# UMN_HASP_2015_Front_End_Board2.net
KiCad netlist of a schematic drawn in EAGLE
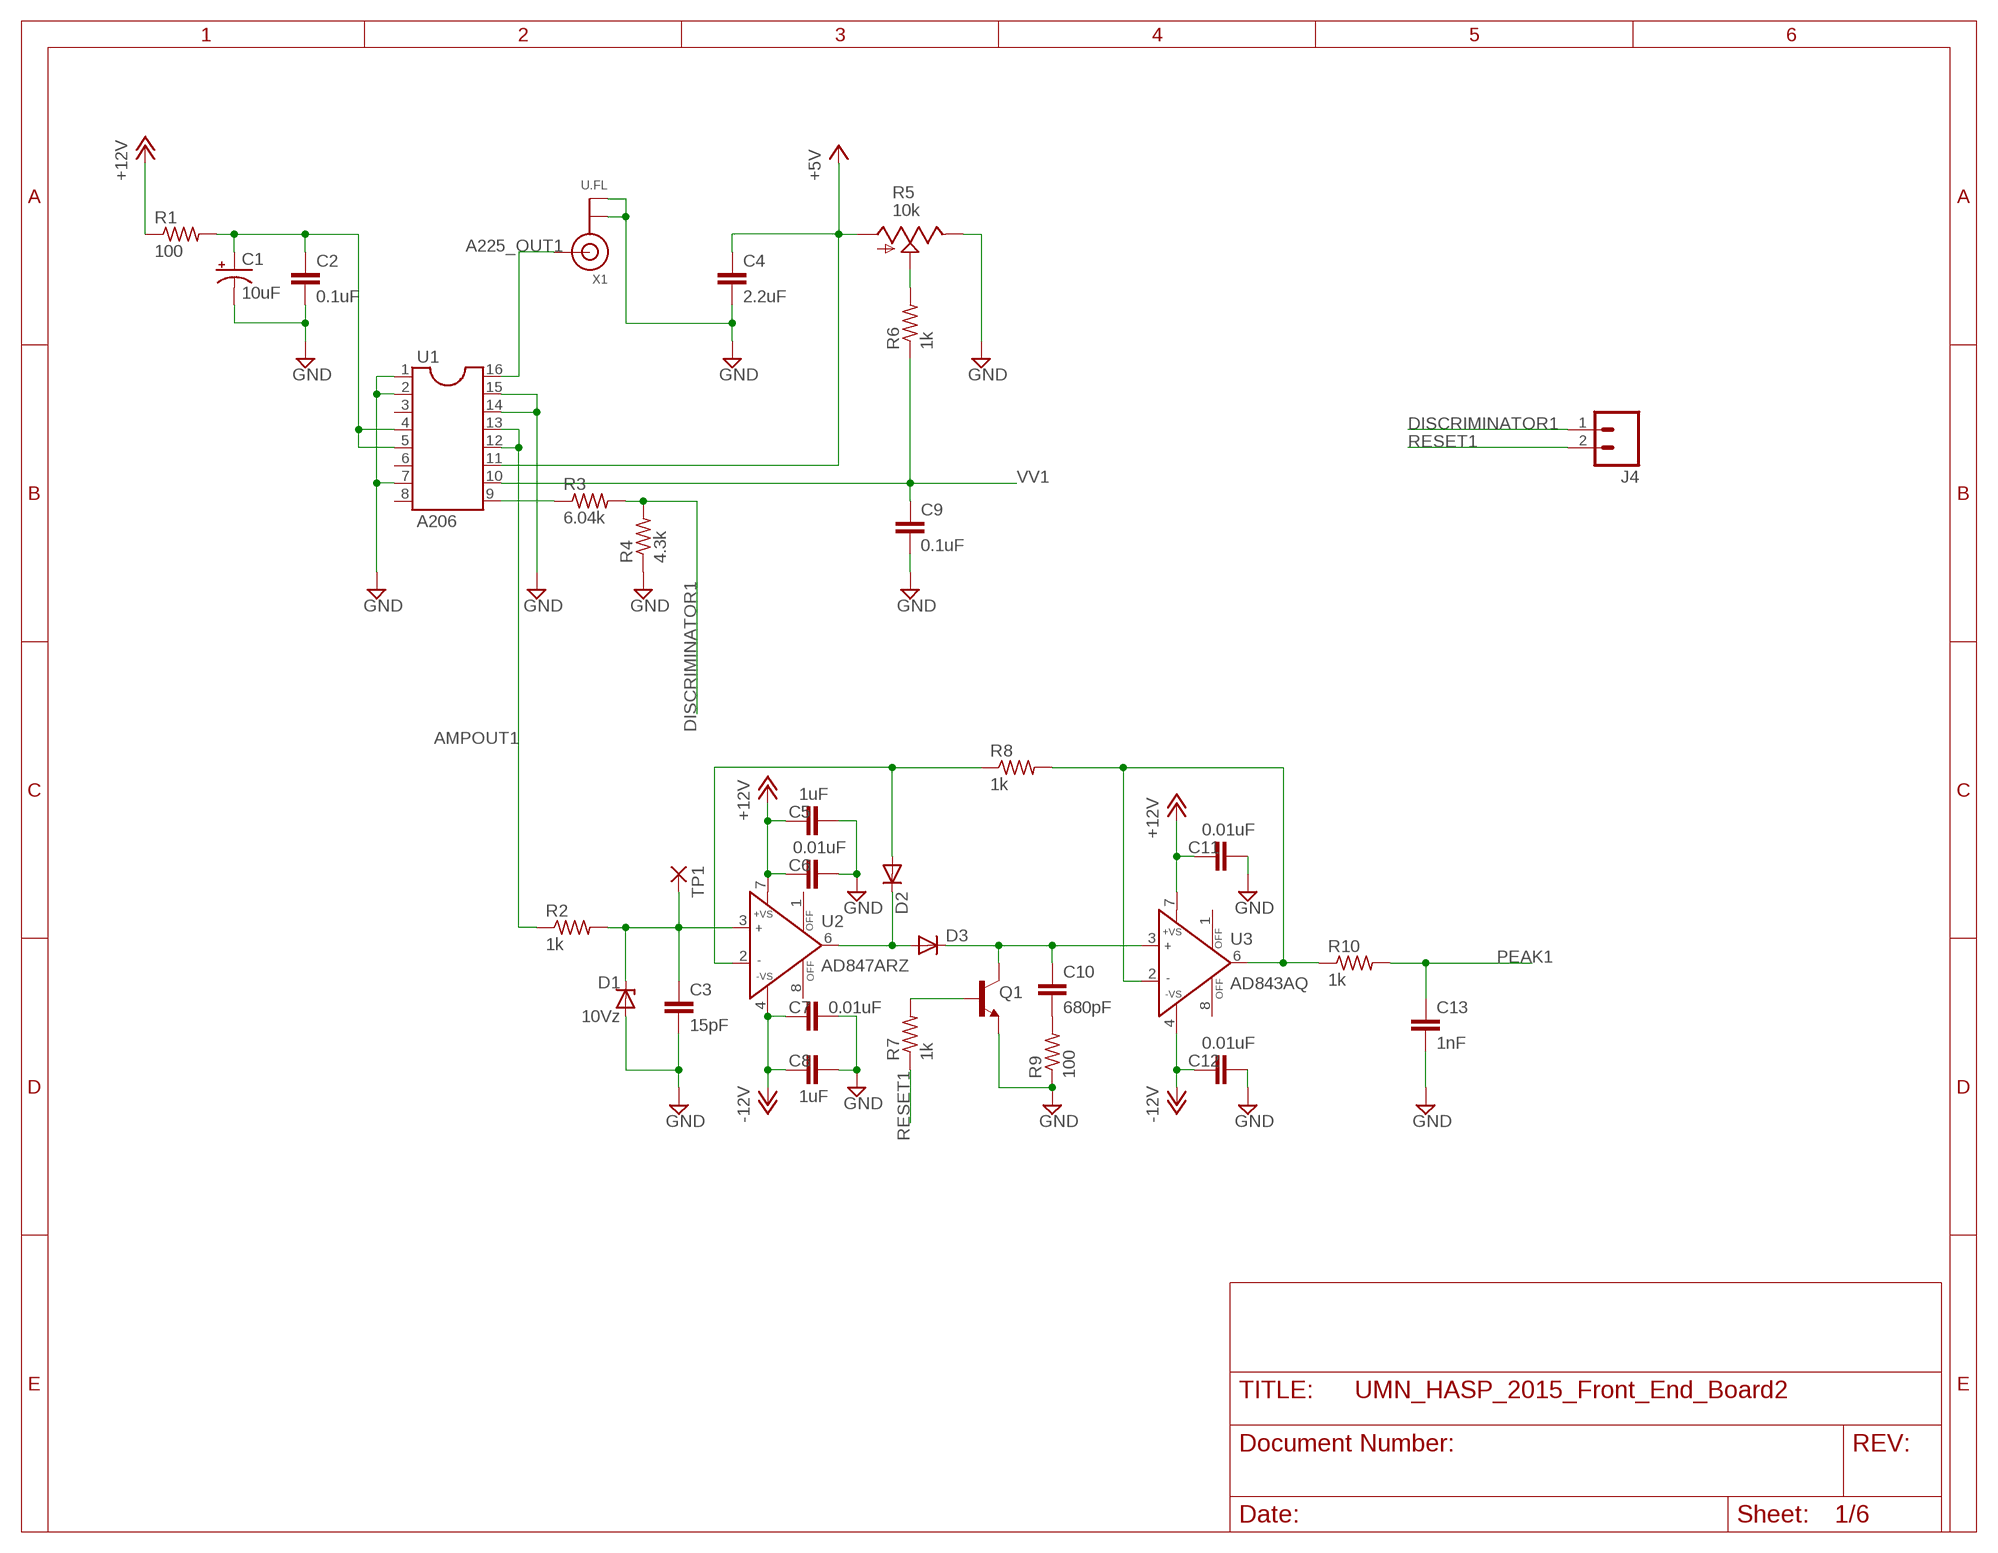
[diagram p0: schematic, sheet 1]
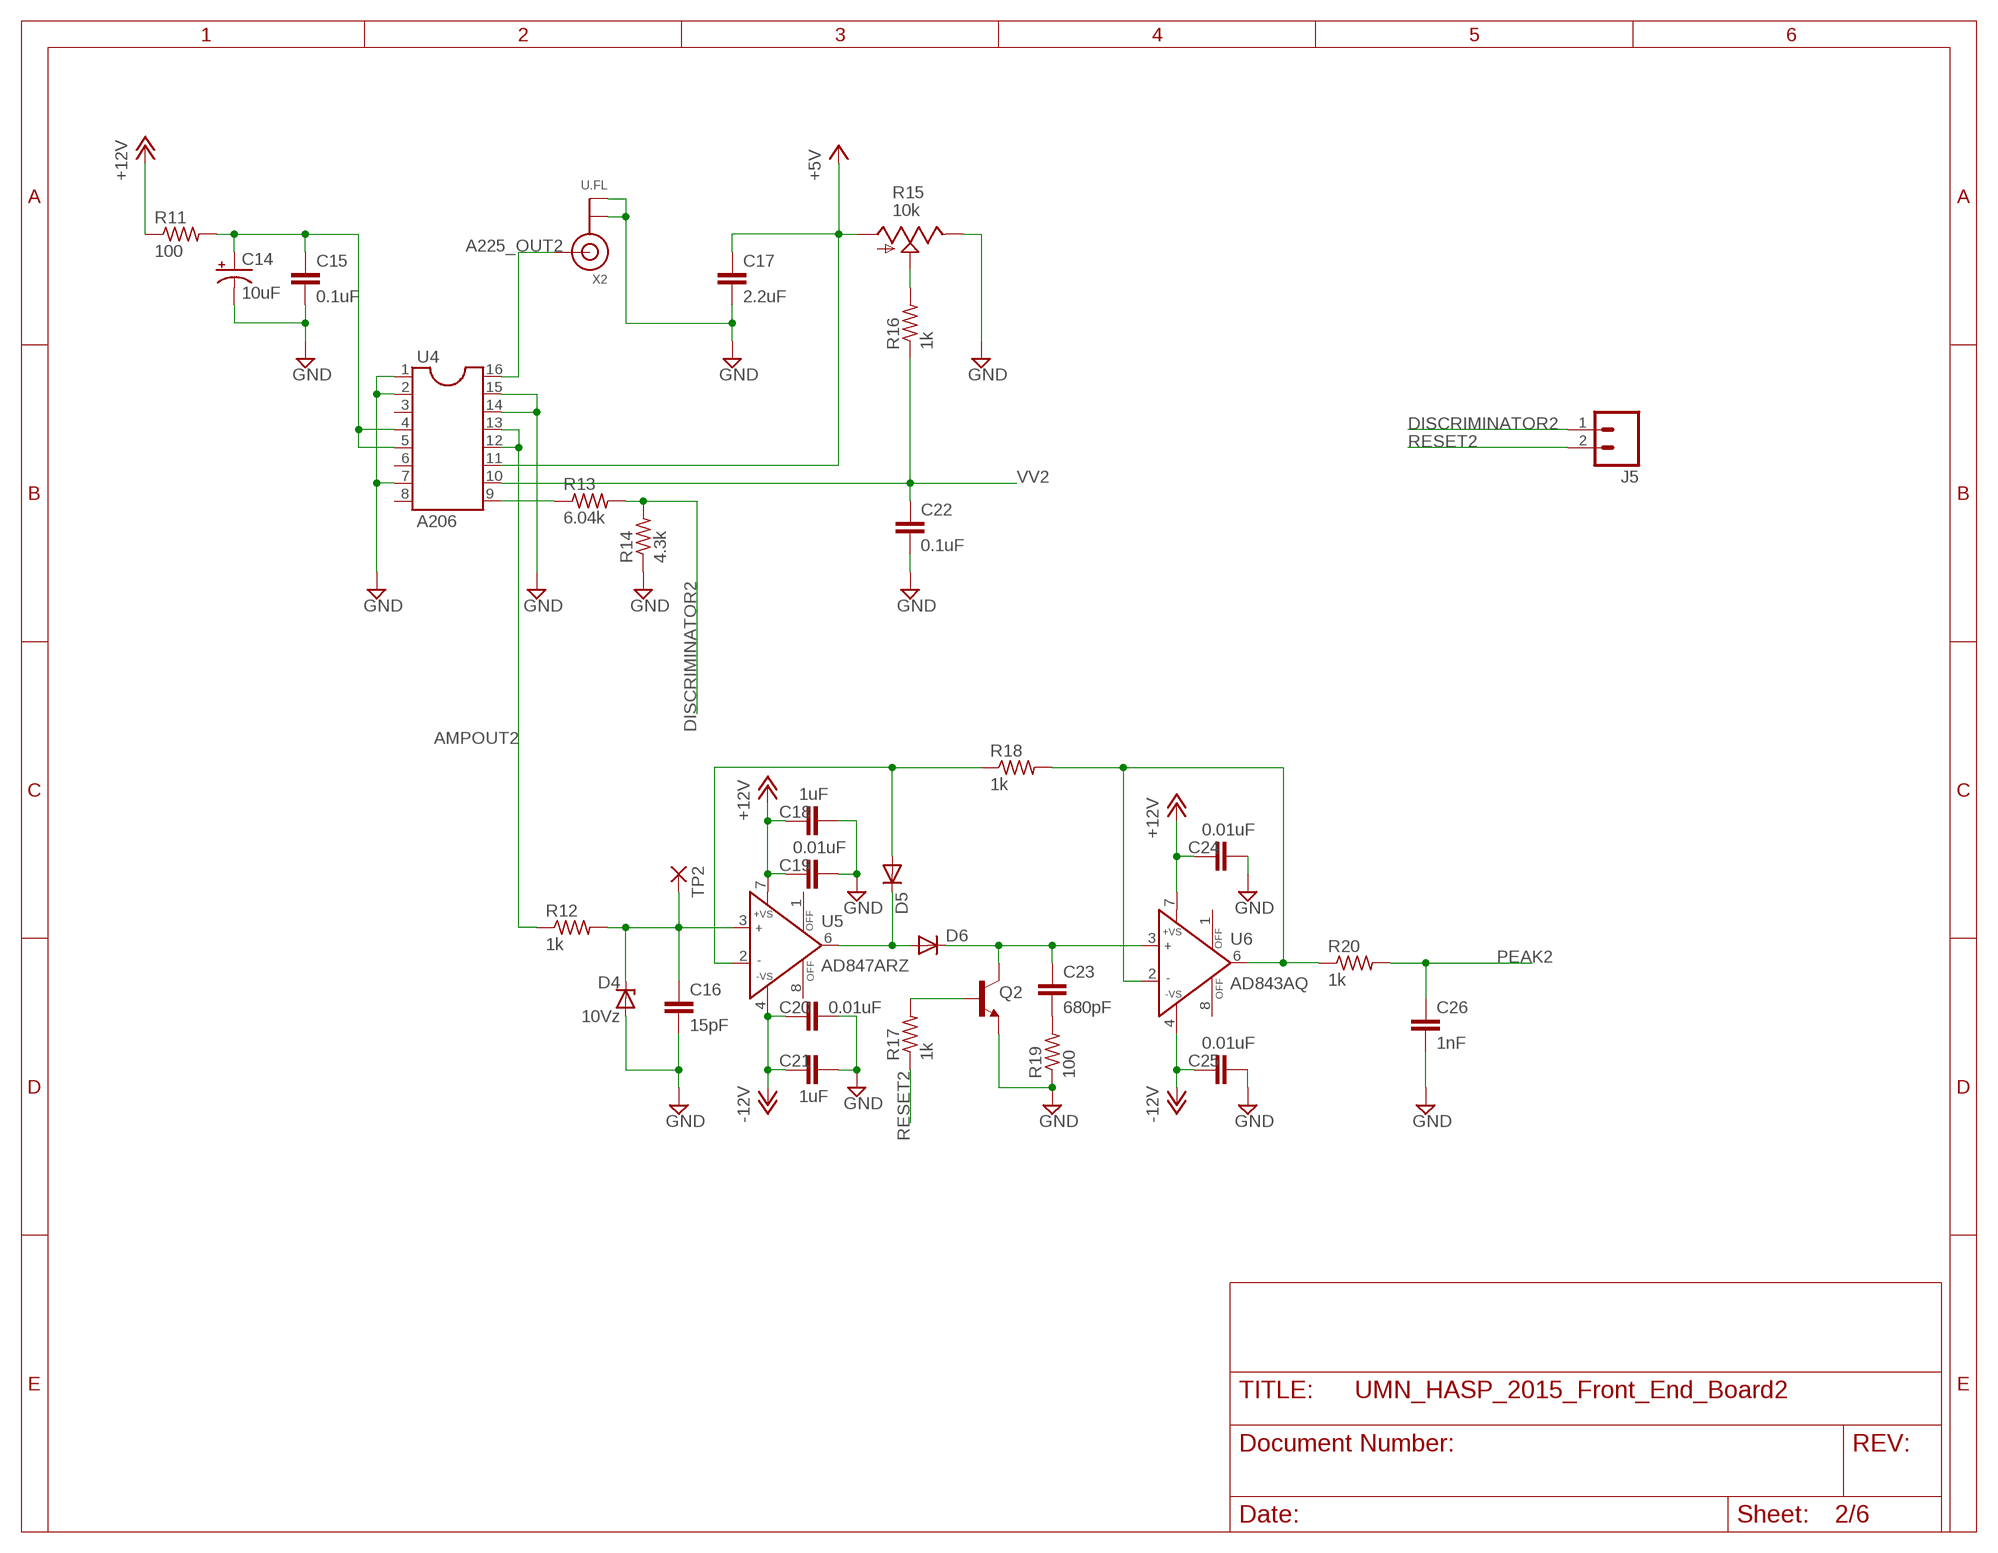
[diagram p1: schematic, sheet 2]
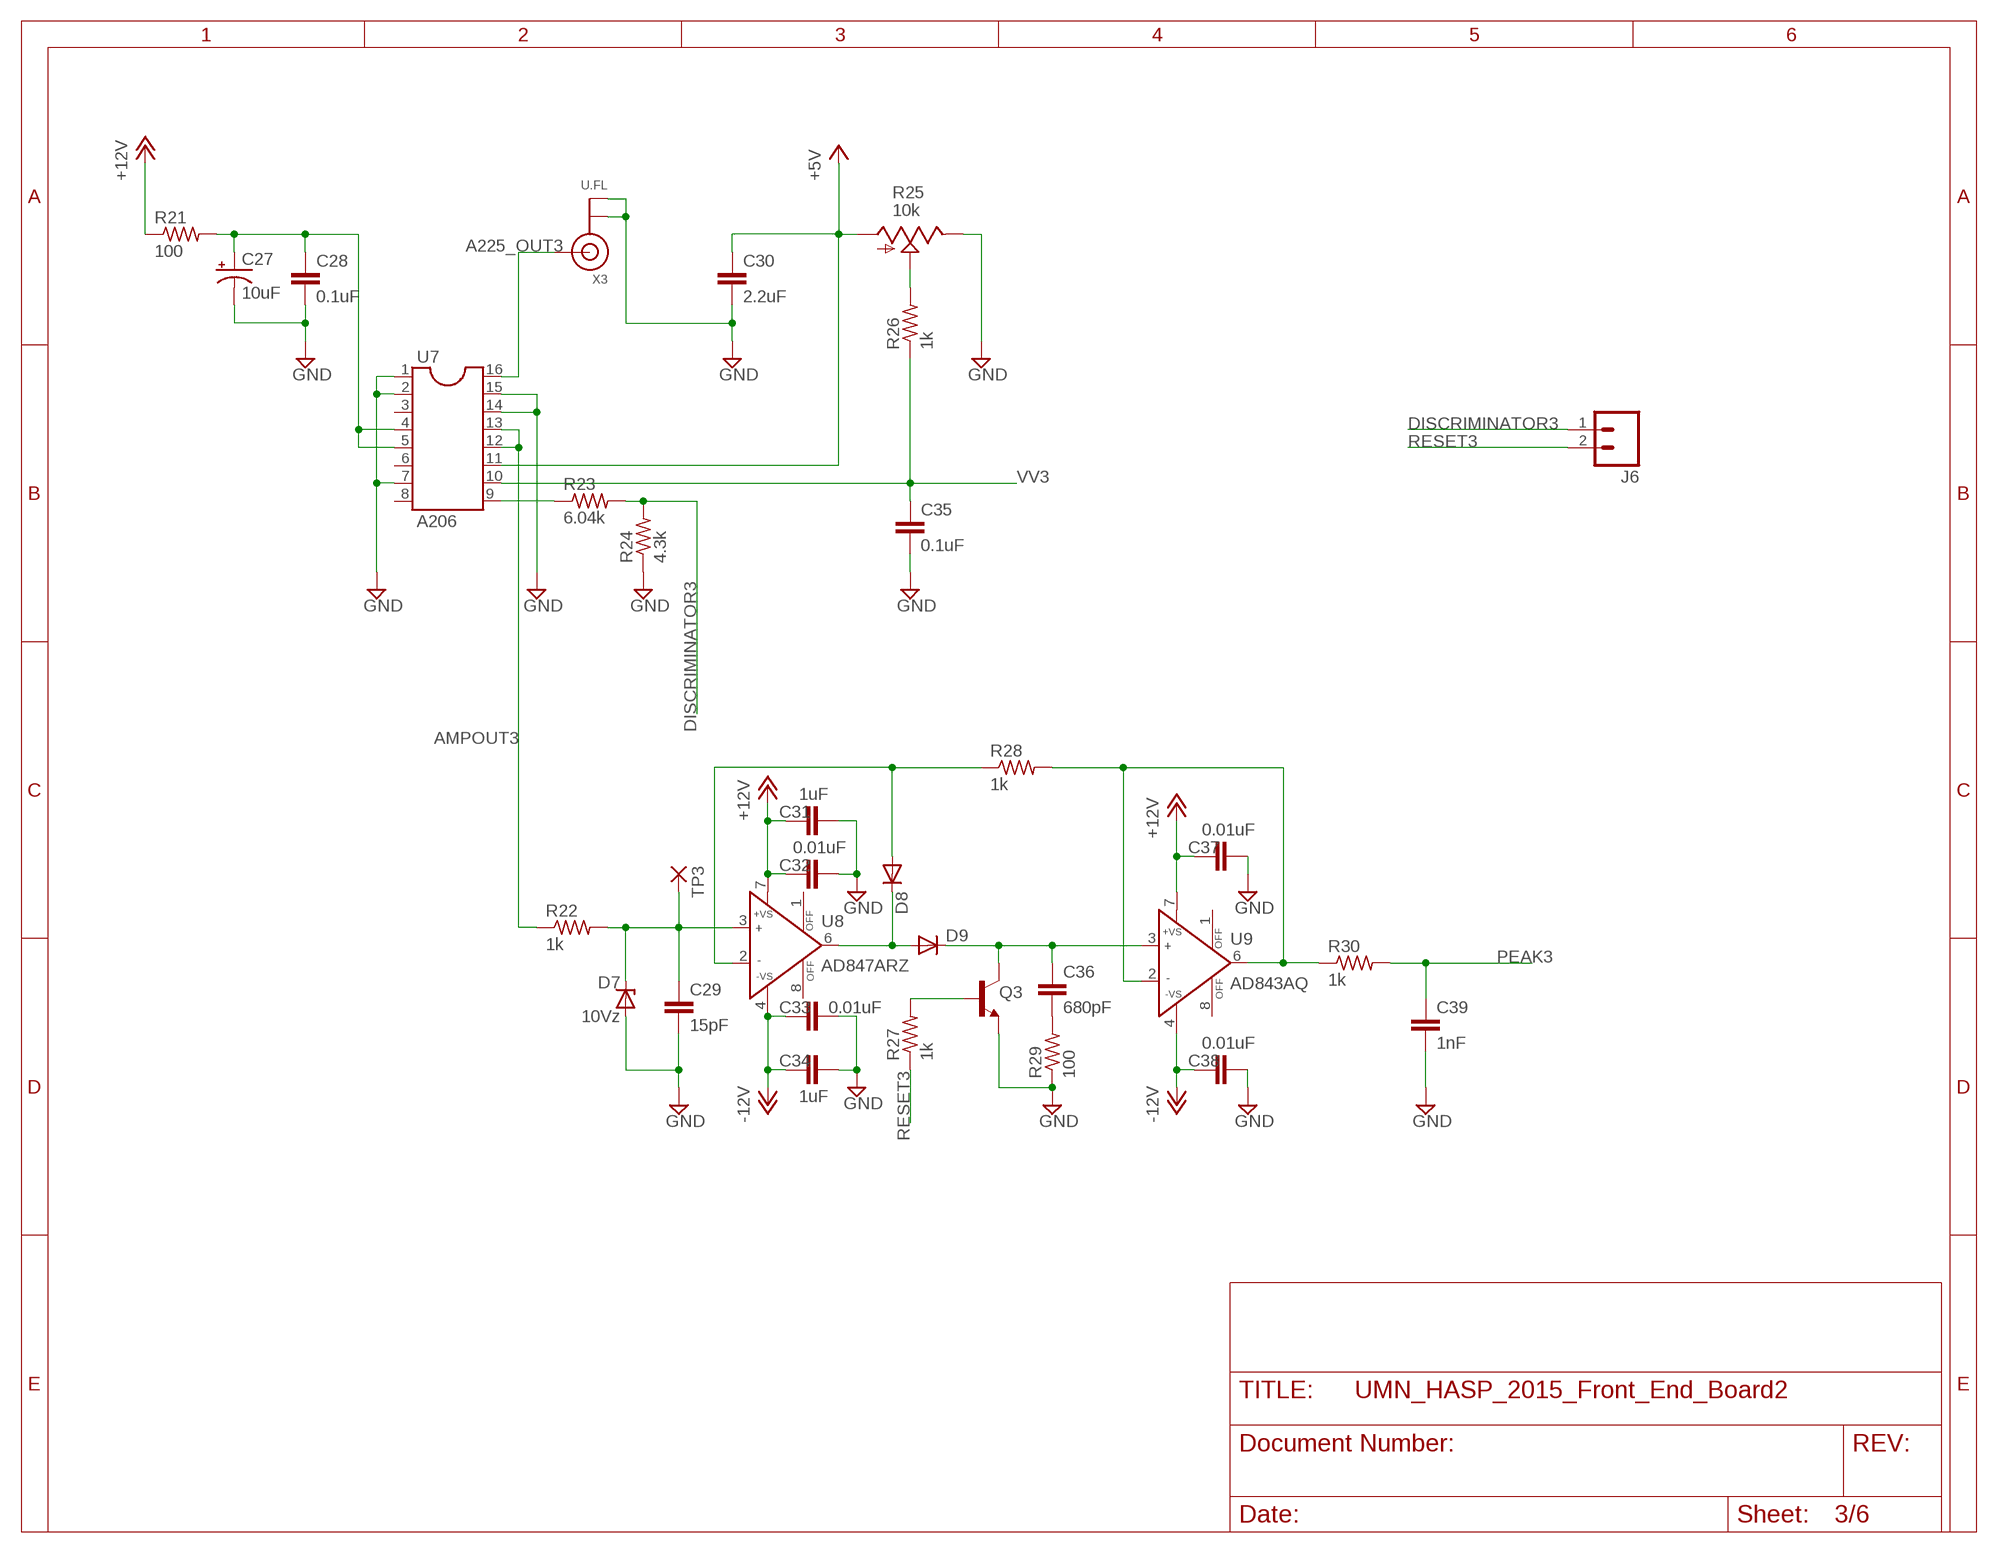
[diagram p2: schematic, sheet 3]
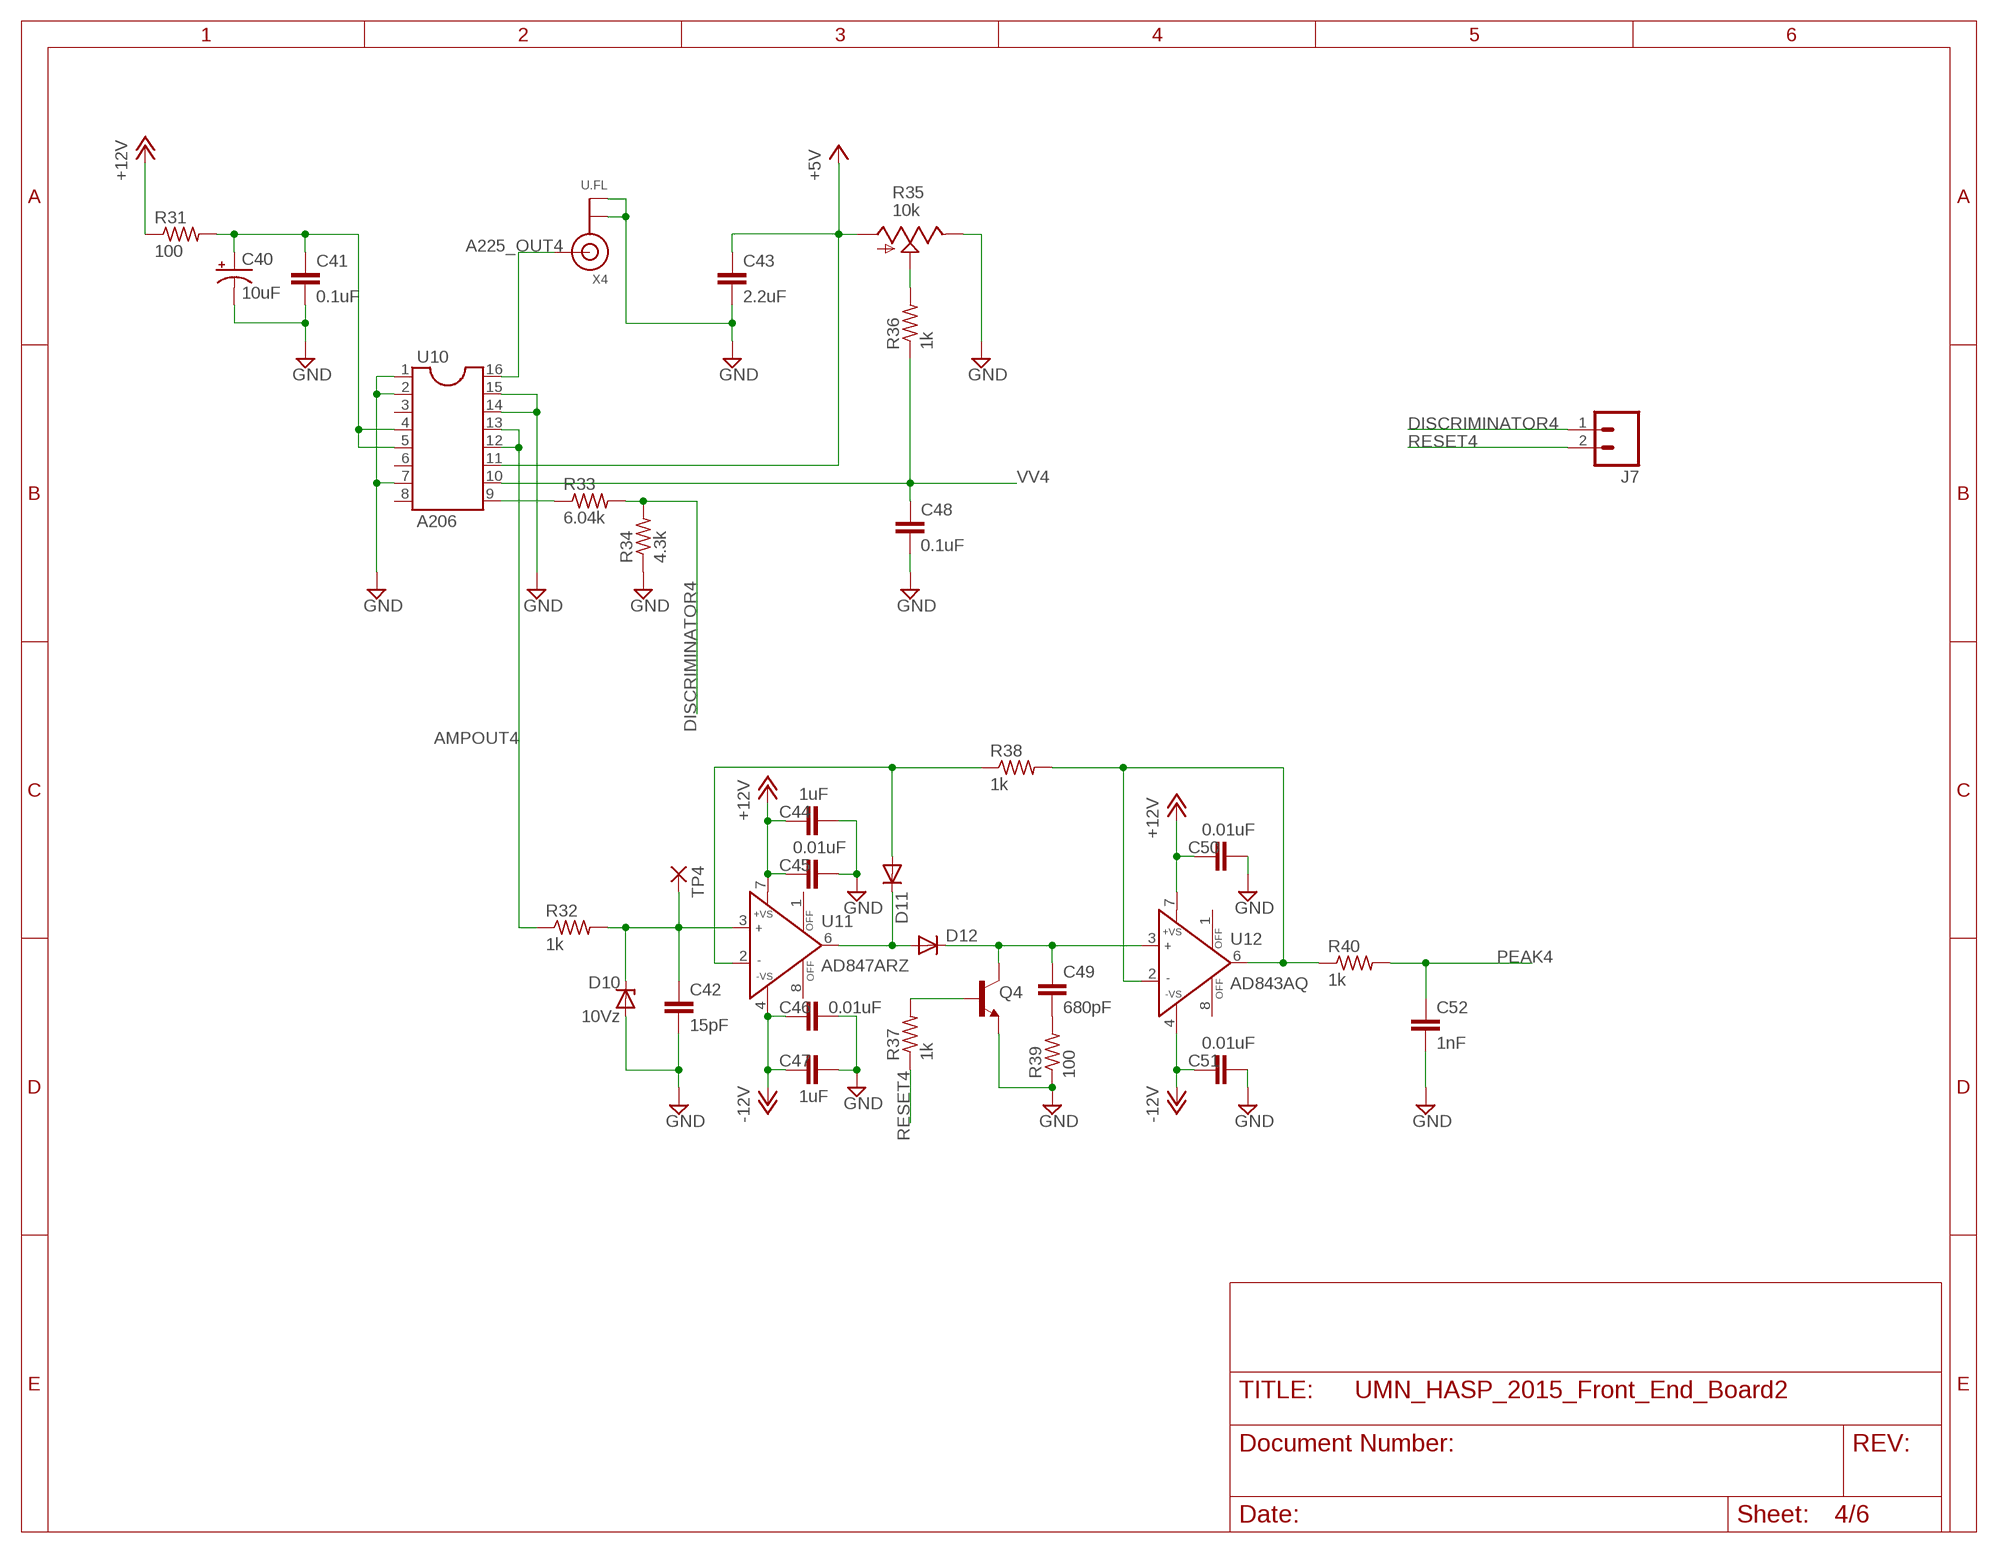
[diagram p3: schematic, sheet 4]
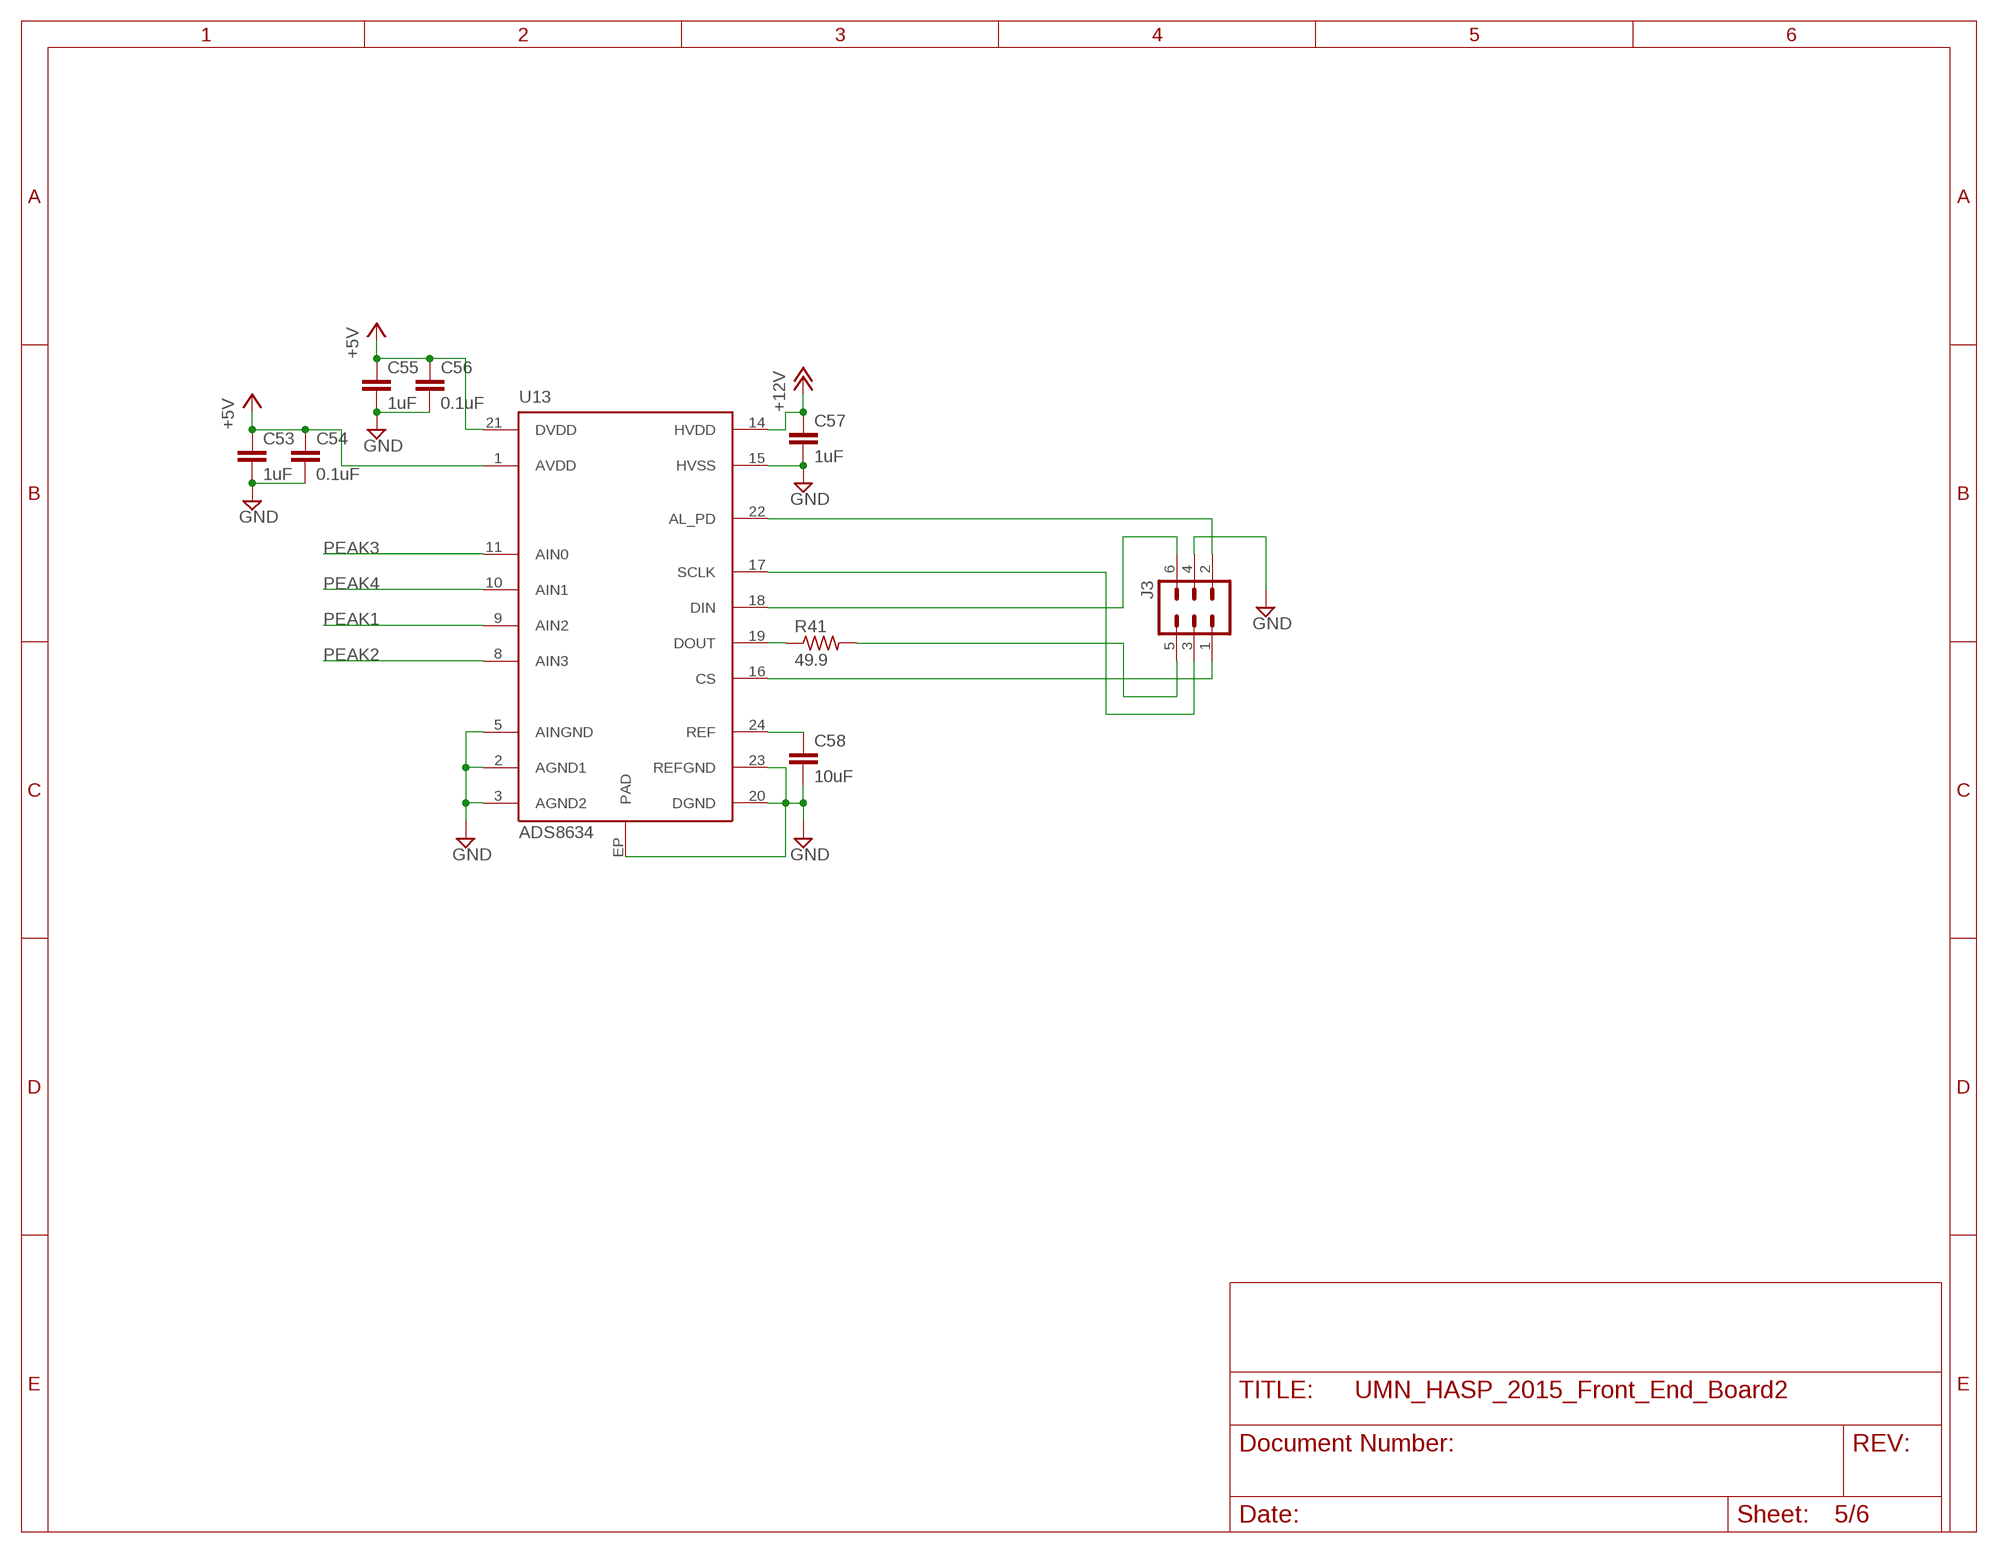
[diagram p4: schematic, sheet 5]
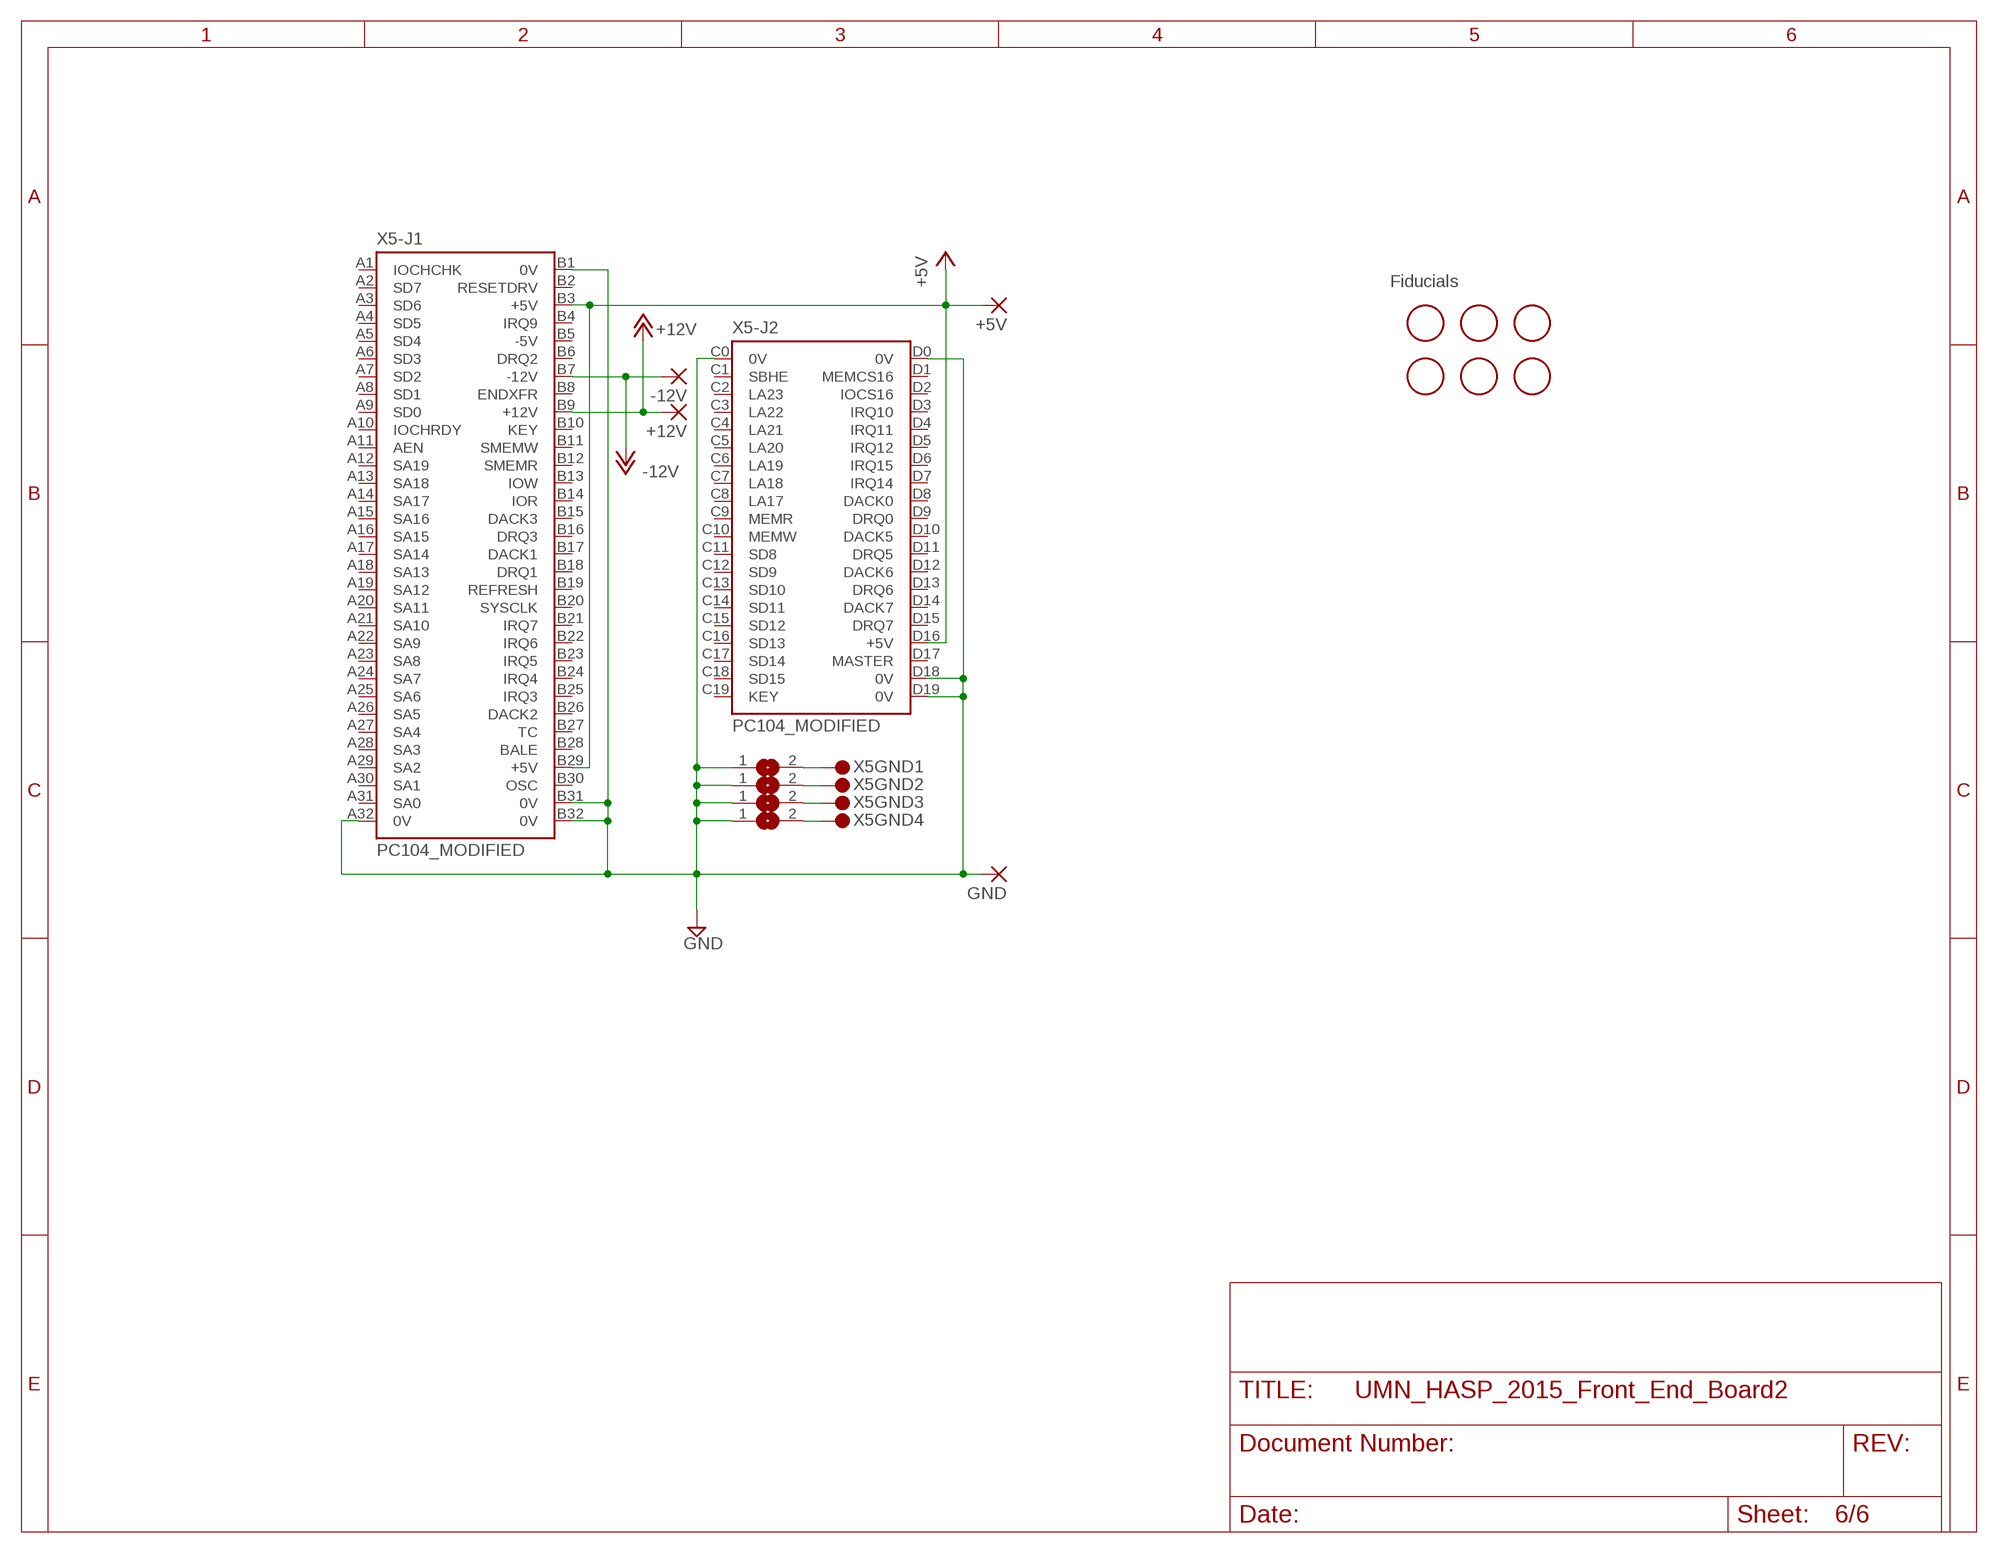
[diagram p5: schematic, sheet 6]

(export (version "E")
  (design (tool "Eeschema 10.0.6"))
  (components
    (comp (ref "C53")
      (value "1uF")
      (footprint "eagle-import:C0402K")
      (libsource (lib "eagle-import") (part "C-EUC0402K"))
    )
    (comp (ref "C54")
      (value "0.1uF")
      (footprint "eagle-import:C0402K")
      (libsource (lib "eagle-import") (part "C-EUC0402K"))
    )
    (comp (ref "C55")
      (value "1uF")
      (footprint "eagle-import:C0402K")
      (libsource (lib "eagle-import") (part "C-EUC0402K"))
    )
    (comp (ref "C56")
      (value "0.1uF")
      (footprint "eagle-import:C0402K")
      (libsource (lib "eagle-import") (part "C-EUC0402K"))
    )
    (comp (ref "C57")
      (value "1uF")
      (footprint "eagle-import:C0402K")
      (libsource (lib "eagle-import") (part "C-EUC0402K"))
    )
    (comp (ref "C58")
      (value "10uF")
      (footprint "eagle-import:C0603K")
      (libsource (lib "eagle-import") (part "C-EUC0603K"))
    )
    (comp (ref "J3")
      (value "MA03-2")
      (footprint "eagle-import:MA03-2")
      (libsource (lib "eagle-import") (part "MA03-2"))
    )
    (comp (ref "R41")
      (value "49.9")
      (footprint "eagle-import:R0402")
      (libsource (lib "eagle-import") (part "R-US_R0402"))
    )
    (comp (ref "U13")
      (value "ADS8634")
      (footprint "eagle-import:QFN24")
      (libsource (lib "eagle-import") (part "ADS8634"))
    )
    (comp (ref "C14")
      (value "10uF")
      (footprint "eagle-import:C_6032-28R")
      (libsource (lib "eagle-import") (part "CPOL-USC/6032-28R"))
    )
    (comp (ref "C15")
      (value "0.1uF")
      (footprint "eagle-import:C0603K")
      (libsource (lib "eagle-import") (part "C-EUC0603K"))
    )
    (comp (ref "C16")
      (value "15pF")
      (footprint "eagle-import:C0402K")
      (libsource (lib "eagle-import") (part "C-EUC0402K"))
    )
    (comp (ref "C17")
      (value "2.2uF")
      (footprint "eagle-import:C0603K")
      (libsource (lib "eagle-import") (part "C-EUC0603K"))
    )
    (comp (ref "C18")
      (value "1uF")
      (footprint "eagle-import:C0603K")
      (libsource (lib "eagle-import") (part "C-EUC0603K"))
    )
    (comp (ref "C19")
      (value "0.01uF")
      (footprint "eagle-import:C0402K")
      (libsource (lib "eagle-import") (part "C-EUC0402K"))
    )
    (comp (ref "C20")
      (value "0.01uF")
      (footprint "eagle-import:C0402K")
      (libsource (lib "eagle-import") (part "C-EUC0402K"))
    )
    (comp (ref "C21")
      (value "1uF")
      (footprint "eagle-import:C0603K")
      (libsource (lib "eagle-import") (part "C-EUC0603K"))
    )
    (comp (ref "C22")
      (value "0.1uF")
      (footprint "eagle-import:C0603K")
      (libsource (lib "eagle-import") (part "C-EUC0603K"))
    )
    (comp (ref "C23")
      (value "680pF")
      (footprint "eagle-import:C0402K")
      (libsource (lib "eagle-import") (part "C-EUC0402K"))
    )
    (comp (ref "C24")
      (value "0.01uF")
      (footprint "eagle-import:C0402K")
      (libsource (lib "eagle-import") (part "C-EUC0402K"))
    )
    (comp (ref "C25")
      (value "0.01uF")
      (footprint "eagle-import:C0402K")
      (libsource (lib "eagle-import") (part "C-EUC0402K"))
    )
    (comp (ref "C26")
      (value "1nF")
      (footprint "eagle-import:C0402K")
      (libsource (lib "eagle-import") (part "C-EUC0402K"))
    )
    (comp (ref "D4")
      (value "10Vz")
      (footprint "eagle-import:SOT23")
      (libsource (lib "eagle-import") (part "ZENER-DIODESOT23"))
    )
    (comp (ref "D5")
      (value "DIODE-SOD323-R")
      (footprint "eagle-import:SOD323-R")
      (libsource (lib "eagle-import") (part "DIODE-SOD323-R"))
    )
    (comp (ref "D6")
      (value "DIODE-SOD323-R")
      (footprint "eagle-import:SOD323-R")
      (libsource (lib "eagle-import") (part "DIODE-SOD323-R"))
    )
    (comp (ref "J5")
      (value "M02PTH")
      (footprint "eagle-import:1X02")
      (libsource (lib "eagle-import") (part "M02PTH"))
    )
    (comp (ref "Q2")
      (value "-NPN-SOT23-EBC")
      (footprint "eagle-import:SOT23-EBC")
      (libsource (lib "eagle-import") (part "-NPN-SOT23-EBC"))
    )
    (comp (ref "R11")
      (value "100")
      (footprint "eagle-import:R0603")
      (libsource (lib "eagle-import") (part "R-US_R0603"))
    )
    (comp (ref "R12")
      (value "1k")
      (footprint "eagle-import:R0603")
      (libsource (lib "eagle-import") (part "R-US_R0603"))
    )
    (comp (ref "R13")
      (value "6.04k")
      (footprint "eagle-import:R0603")
      (libsource (lib "eagle-import") (part "R-US_R0603"))
    )
    (comp (ref "R14")
      (value "4.3k")
      (footprint "eagle-import:R0603")
      (libsource (lib "eagle-import") (part "R-US_R0603"))
    )
    (comp (ref "R15")
      (value "10k")
      (footprint "eagle-import:3223J")
      (libsource (lib "eagle-import") (part "TRIM_US-3223J"))
    )
    (comp (ref "R16")
      (value "1k")
      (footprint "eagle-import:R0603")
      (libsource (lib "eagle-import") (part "R-US_R0603"))
    )
    (comp (ref "R17")
      (value "1k")
      (footprint "eagle-import:R0603")
      (libsource (lib "eagle-import") (part "R-US_R0603"))
    )
    (comp (ref "R18")
      (value "1k")
      (footprint "eagle-import:R0603")
      (libsource (lib "eagle-import") (part "R-US_R0603"))
    )
    (comp (ref "R19")
      (value "100")
      (footprint "eagle-import:R0603")
      (libsource (lib "eagle-import") (part "R-US_R0603"))
    )
    (comp (ref "R20")
      (value "1k")
      (footprint "eagle-import:R0402")
      (libsource (lib "eagle-import") (part "R-US_R0402"))
    )
    (comp (ref "TP2")
      (value "SMD2")
      (footprint "eagle-import:SMD1,27-2,54")
      (libsource (lib "eagle-import") (part "SMD2"))
    )
    (comp (ref "U4")
      (value "A206")
      (footprint "eagle-import:SOCKET-16")
      (libsource (lib "eagle-import") (part "DIL16S"))
    )
    (comp (ref "U5")
      (value "AD847ARZ")
      (footprint "eagle-import:SO8")
      (libsource (lib "eagle-import") (part "AD847ARZ"))
    )
    (comp (ref "U6")
      (value "AD843AQ")
      (footprint "eagle-import:DIL08")
      (libsource (lib "eagle-import") (part "AD843AQ"))
    )
    (comp (ref "X2")
      (value "U.FL")
      (footprint "eagle-import:U.FL")
      (libsource (lib "eagle-import") (part "ANTENNA_U.FL"))
    )
    (comp (ref "C40")
      (value "10uF")
      (footprint "eagle-import:C_6032-28R")
      (libsource (lib "eagle-import") (part "CPOL-USC/6032-28R"))
    )
    (comp (ref "C41")
      (value "0.1uF")
      (footprint "eagle-import:C0603K")
      (libsource (lib "eagle-import") (part "C-EUC0603K"))
    )
    (comp (ref "C42")
      (value "15pF")
      (footprint "eagle-import:C0402K")
      (libsource (lib "eagle-import") (part "C-EUC0402K"))
    )
    (comp (ref "C43")
      (value "2.2uF")
      (footprint "eagle-import:C0603K")
      (libsource (lib "eagle-import") (part "C-EUC0603K"))
    )
    (comp (ref "C44")
      (value "1uF")
      (footprint "eagle-import:C0603K")
      (libsource (lib "eagle-import") (part "C-EUC0603K"))
    )
    (comp (ref "C45")
      (value "0.01uF")
      (footprint "eagle-import:C0402K")
      (libsource (lib "eagle-import") (part "C-EUC0402K"))
    )
    (comp (ref "C46")
      (value "0.01uF")
      (footprint "eagle-import:C0402K")
      (libsource (lib "eagle-import") (part "C-EUC0402K"))
    )
    (comp (ref "C47")
      (value "1uF")
      (footprint "eagle-import:C0603K")
      (libsource (lib "eagle-import") (part "C-EUC0603K"))
    )
    (comp (ref "C48")
      (value "0.1uF")
      (footprint "eagle-import:C0603K")
      (libsource (lib "eagle-import") (part "C-EUC0603K"))
    )
    (comp (ref "C49")
      (value "680pF")
      (footprint "eagle-import:C0402K")
      (libsource (lib "eagle-import") (part "C-EUC0402K"))
    )
    (comp (ref "C50")
      (value "0.01uF")
      (footprint "eagle-import:C0402K")
      (libsource (lib "eagle-import") (part "C-EUC0402K"))
    )
    (comp (ref "C51")
      (value "0.01uF")
      (footprint "eagle-import:C0402K")
      (libsource (lib "eagle-import") (part "C-EUC0402K"))
    )
    (comp (ref "C52")
      (value "1nF")
      (footprint "eagle-import:C0402K")
      (libsource (lib "eagle-import") (part "C-EUC0402K"))
    )
    (comp (ref "D10")
      (value "10Vz")
      (footprint "eagle-import:SOT23")
      (libsource (lib "eagle-import") (part "ZENER-DIODESOT23"))
    )
    (comp (ref "D11")
      (value "DIODE-SOD323-R")
      (footprint "eagle-import:SOD323-R")
      (libsource (lib "eagle-import") (part "DIODE-SOD323-R"))
    )
    (comp (ref "D12")
      (value "DIODE-SOD323-R")
      (footprint "eagle-import:SOD323-R")
      (libsource (lib "eagle-import") (part "DIODE-SOD323-R"))
    )
    (comp (ref "J7")
      (value "M02PTH")
      (footprint "eagle-import:1X02")
      (libsource (lib "eagle-import") (part "M02PTH"))
    )
    (comp (ref "Q4")
      (value "-NPN-SOT23-EBC")
      (footprint "eagle-import:SOT23-EBC")
      (libsource (lib "eagle-import") (part "-NPN-SOT23-EBC"))
    )
    (comp (ref "R31")
      (value "100")
      (footprint "eagle-import:R0603")
      (libsource (lib "eagle-import") (part "R-US_R0603"))
    )
    (comp (ref "R32")
      (value "1k")
      (footprint "eagle-import:R0603")
      (libsource (lib "eagle-import") (part "R-US_R0603"))
    )
    (comp (ref "R33")
      (value "6.04k")
      (footprint "eagle-import:R0603")
      (libsource (lib "eagle-import") (part "R-US_R0603"))
    )
    (comp (ref "R34")
      (value "4.3k")
      (footprint "eagle-import:R0603")
      (libsource (lib "eagle-import") (part "R-US_R0603"))
    )
    (comp (ref "R35")
      (value "10k")
      (footprint "eagle-import:3223J")
      (libsource (lib "eagle-import") (part "TRIM_US-3223J"))
    )
    (comp (ref "R36")
      (value "1k")
      (footprint "eagle-import:R0603")
      (libsource (lib "eagle-import") (part "R-US_R0603"))
    )
    (comp (ref "R37")
      (value "1k")
      (footprint "eagle-import:R0603")
      (libsource (lib "eagle-import") (part "R-US_R0603"))
    )
    (comp (ref "R38")
      (value "1k")
      (footprint "eagle-import:R0603")
      (libsource (lib "eagle-import") (part "R-US_R0603"))
    )
    (comp (ref "R39")
      (value "100")
      (footprint "eagle-import:R0603")
      (libsource (lib "eagle-import") (part "R-US_R0603"))
    )
    (comp (ref "R40")
      (value "1k")
      (footprint "eagle-import:R0402")
      (libsource (lib "eagle-import") (part "R-US_R0402"))
    )
    (comp (ref "TP4")
      (value "SMD2")
      (footprint "eagle-import:SMD1,27-2,54")
      (libsource (lib "eagle-import") (part "SMD2"))
    )
    (comp (ref "U10")
      (value "A206")
      (footprint "eagle-import:SOCKET-16")
      (libsource (lib "eagle-import") (part "DIL16S"))
    )
    (comp (ref "U11")
      (value "AD847ARZ")
      (footprint "eagle-import:SO8")
      (libsource (lib "eagle-import") (part "AD847ARZ"))
    )
    (comp (ref "U12")
      (value "AD843AQ")
      (footprint "eagle-import:DIL08")
      (libsource (lib "eagle-import") (part "AD843AQ"))
    )
    (comp (ref "X4")
      (value "U.FL")
      (footprint "eagle-import:U.FL")
      (libsource (lib "eagle-import") (part "ANTENNA_U.FL"))
    )
    (comp (ref "C27")
      (value "10uF")
      (footprint "eagle-import:C_6032-28R")
      (libsource (lib "eagle-import") (part "CPOL-USC/6032-28R"))
    )
    (comp (ref "C28")
      (value "0.1uF")
      (footprint "eagle-import:C0603K")
      (libsource (lib "eagle-import") (part "C-EUC0603K"))
    )
    (comp (ref "C29")
      (value "15pF")
      (footprint "eagle-import:C0402K")
      (libsource (lib "eagle-import") (part "C-EUC0402K"))
    )
    (comp (ref "C30")
      (value "2.2uF")
      (footprint "eagle-import:C0603K")
      (libsource (lib "eagle-import") (part "C-EUC0603K"))
    )
    (comp (ref "C31")
      (value "1uF")
      (footprint "eagle-import:C0603K")
      (libsource (lib "eagle-import") (part "C-EUC0603K"))
    )
    (comp (ref "C32")
      (value "0.01uF")
      (footprint "eagle-import:C0402K")
      (libsource (lib "eagle-import") (part "C-EUC0402K"))
    )
    (comp (ref "C33")
      (value "0.01uF")
      (footprint "eagle-import:C0402K")
      (libsource (lib "eagle-import") (part "C-EUC0402K"))
    )
    (comp (ref "C34")
      (value "1uF")
      (footprint "eagle-import:C0603K")
      (libsource (lib "eagle-import") (part "C-EUC0603K"))
    )
    (comp (ref "C35")
      (value "0.1uF")
      (footprint "eagle-import:C0603K")
      (libsource (lib "eagle-import") (part "C-EUC0603K"))
    )
    (comp (ref "C36")
      (value "680pF")
      (footprint "eagle-import:C0402K")
      (libsource (lib "eagle-import") (part "C-EUC0402K"))
    )
    (comp (ref "C37")
      (value "0.01uF")
      (footprint "eagle-import:C0402K")
      (libsource (lib "eagle-import") (part "C-EUC0402K"))
    )
    (comp (ref "C38")
      (value "0.01uF")
      (footprint "eagle-import:C0402K")
      (libsource (lib "eagle-import") (part "C-EUC0402K"))
    )
    (comp (ref "C39")
      (value "1nF")
      (footprint "eagle-import:C0402K")
      (libsource (lib "eagle-import") (part "C-EUC0402K"))
    )
    (comp (ref "D7")
      (value "10Vz")
      (footprint "eagle-import:SOT23")
      (libsource (lib "eagle-import") (part "ZENER-DIODESOT23"))
    )
    (comp (ref "D8")
      (value "DIODE-SOD323-R")
      (footprint "eagle-import:SOD323-R")
      (libsource (lib "eagle-import") (part "DIODE-SOD323-R"))
    )
    (comp (ref "D9")
      (value "DIODE-SOD323-R")
      (footprint "eagle-import:SOD323-R")
      (libsource (lib "eagle-import") (part "DIODE-SOD323-R"))
    )
    (comp (ref "J6")
      (value "M02PTH")
      (footprint "eagle-import:1X02")
      (libsource (lib "eagle-import") (part "M02PTH"))
    )
    (comp (ref "Q3")
      (value "-NPN-SOT23-EBC")
      (footprint "eagle-import:SOT23-EBC")
      (libsource (lib "eagle-import") (part "-NPN-SOT23-EBC"))
    )
    (comp (ref "R21")
      (value "100")
      (footprint "eagle-import:R0603")
      (libsource (lib "eagle-import") (part "R-US_R0603"))
    )
    (comp (ref "R22")
      (value "1k")
      (footprint "eagle-import:R0603")
      (libsource (lib "eagle-import") (part "R-US_R0603"))
    )
    (comp (ref "R23")
      (value "6.04k")
      (footprint "eagle-import:R0603")
      (libsource (lib "eagle-import") (part "R-US_R0603"))
    )
    (comp (ref "R24")
      (value "4.3k")
      (footprint "eagle-import:R0603")
      (libsource (lib "eagle-import") (part "R-US_R0603"))
    )
    (comp (ref "R25")
      (value "10k")
      (footprint "eagle-import:3223J")
      (libsource (lib "eagle-import") (part "TRIM_US-3223J"))
    )
    (comp (ref "R26")
      (value "1k")
      (footprint "eagle-import:R0603")
      (libsource (lib "eagle-import") (part "R-US_R0603"))
    )
    (comp (ref "R27")
      (value "1k")
      (footprint "eagle-import:R0603")
      (libsource (lib "eagle-import") (part "R-US_R0603"))
    )
    (comp (ref "R28")
      (value "1k")
      (footprint "eagle-import:R0603")
      (libsource (lib "eagle-import") (part "R-US_R0603"))
    )
    (comp (ref "R29")
      (value "100")
      (footprint "eagle-import:R0603")
      (libsource (lib "eagle-import") (part "R-US_R0603"))
    )
    (comp (ref "R30")
      (value "1k")
      (footprint "eagle-import:R0402")
      (libsource (lib "eagle-import") (part "R-US_R0402"))
    )
    (comp (ref "TP3")
      (value "SMD2")
      (footprint "eagle-import:SMD1,27-2,54")
      (libsource (lib "eagle-import") (part "SMD2"))
    )
    (comp (ref "U7")
      (value "A206")
      (footprint "eagle-import:SOCKET-16")
      (libsource (lib "eagle-import") (part "DIL16S"))
    )
    (comp (ref "U8")
      (value "AD847ARZ")
      (footprint "eagle-import:SO8")
      (libsource (lib "eagle-import") (part "AD847ARZ"))
    )
    (comp (ref "U9")
      (value "AD843AQ")
      (footprint "eagle-import:DIL08")
      (libsource (lib "eagle-import") (part "AD843AQ"))
    )
    (comp (ref "X3")
      (value "U.FL")
      (footprint "eagle-import:U.FL")
      (libsource (lib "eagle-import") (part "ANTENNA_U.FL"))
    )
    (comp (ref "+5V")
      (value "SMD2")
      (footprint "eagle-import:SMD1,27-2,54")
      (libsource (lib "eagle-import") (part "SMD2"))
    )
    (comp (ref "+12V")
      (value "SMD2")
      (footprint "eagle-import:SMD1,27-2,54")
      (libsource (lib "eagle-import") (part "SMD2"))
    )
    (comp (ref "-12V")
      (value "SMD2")
      (footprint "eagle-import:SMD1,27-2,54")
      (libsource (lib "eagle-import") (part "SMD2"))
    )
    (comp (ref "F1")
      (value "FIDUCIAL")
      (footprint "eagle-import:FIDUCIAL_1MM")
      (libsource (lib "eagle-import") (part "FIDUCIAL"))
    )
    (comp (ref "F2")
      (value "FIDUCIAL")
      (footprint "eagle-import:FIDUCIAL_1MM")
      (libsource (lib "eagle-import") (part "FIDUCIAL"))
    )
    (comp (ref "F3")
      (value "FIDUCIAL")
      (footprint "eagle-import:FIDUCIAL_1MM")
      (libsource (lib "eagle-import") (part "FIDUCIAL"))
    )
    (comp (ref "F4")
      (value "FIDUCIAL")
      (footprint "eagle-import:FIDUCIAL_1MM")
      (libsource (lib "eagle-import") (part "FIDUCIAL"))
    )
    (comp (ref "F5")
      (value "FIDUCIAL")
      (footprint "eagle-import:FIDUCIAL_1MM")
      (libsource (lib "eagle-import") (part "FIDUCIAL"))
    )
    (comp (ref "F6")
      (value "FIDUCIAL")
      (footprint "eagle-import:FIDUCIAL_1MM")
      (libsource (lib "eagle-import") (part "FIDUCIAL"))
    )
    (comp (ref "GND")
      (value "SMD2")
      (footprint "eagle-import:SMD1,27-2,54")
      (libsource (lib "eagle-import") (part "SMD2"))
    )
    (comp (ref "SJ1") (value "SJ") (footprint "eagle-import:SJ") (libsource (lib "eagle-import") (part "SJ")))
    (comp (ref "SJ2") (value "SJ") (footprint "eagle-import:SJ") (libsource (lib "eagle-import") (part "SJ")))
    (comp (ref "SJ3") (value "SJ") (footprint "eagle-import:SJ") (libsource (lib "eagle-import") (part "SJ")))
    (comp (ref "SJ4") (value "SJ") (footprint "eagle-import:SJ") (libsource (lib "eagle-import") (part "SJ")))
    (comp (ref "X5")
      (value "PC104_MODIFIED")
      (footprint "eagle-import:PC104_MODIFIED")
      (libsource (lib "eagle-import") (part "PC104_MODIFIED"))
    )
    (comp (ref "C1")
      (value "10uF")
      (footprint "eagle-import:C_6032-28R")
      (libsource (lib "eagle-import") (part "CPOL-USC/6032-28R"))
    )
    (comp (ref "C2")
      (value "0.1uF")
      (footprint "eagle-import:C0603K")
      (libsource (lib "eagle-import") (part "C-EUC0603K"))
    )
    (comp (ref "C3")
      (value "15pF")
      (footprint "eagle-import:C0402K")
      (libsource (lib "eagle-import") (part "C-EUC0402K"))
    )
    (comp (ref "C4")
      (value "2.2uF")
      (footprint "eagle-import:C0603K")
      (libsource (lib "eagle-import") (part "C-EUC0603K"))
    )
    (comp (ref "C5")
      (value "1uF")
      (footprint "eagle-import:C0603K")
      (libsource (lib "eagle-import") (part "C-EUC0603K"))
    )
    (comp (ref "C6")
      (value "0.01uF")
      (footprint "eagle-import:C0402K")
      (libsource (lib "eagle-import") (part "C-EUC0402K"))
    )
    (comp (ref "C7")
      (value "0.01uF")
      (footprint "eagle-import:C0402K")
      (libsource (lib "eagle-import") (part "C-EUC0402K"))
    )
    (comp (ref "C8")
      (value "1uF")
      (footprint "eagle-import:C0603K")
      (libsource (lib "eagle-import") (part "C-EUC0603K"))
    )
    (comp (ref "C9")
      (value "0.1uF")
      (footprint "eagle-import:C0603K")
      (libsource (lib "eagle-import") (part "C-EUC0603K"))
    )
    (comp (ref "C10")
      (value "680pF")
      (footprint "eagle-import:C0402K")
      (libsource (lib "eagle-import") (part "C-EUC0402K"))
    )
    (comp (ref "C11")
      (value "0.01uF")
      (footprint "eagle-import:C0402K")
      (libsource (lib "eagle-import") (part "C-EUC0402K"))
    )
    (comp (ref "C12")
      (value "0.01uF")
      (footprint "eagle-import:C0402K")
      (libsource (lib "eagle-import") (part "C-EUC0402K"))
    )
    (comp (ref "C13")
      (value "1nF")
      (footprint "eagle-import:C0402K")
      (libsource (lib "eagle-import") (part "C-EUC0402K"))
    )
    (comp (ref "D1")
      (value "10Vz")
      (footprint "eagle-import:SOT23")
      (libsource (lib "eagle-import") (part "ZENER-DIODESOT23"))
    )
    (comp (ref "D2")
      (value "DIODE-SOD323-R")
      (footprint "eagle-import:SOD323-R")
      (libsource (lib "eagle-import") (part "DIODE-SOD323-R"))
    )
    (comp (ref "D3")
      (value "DIODE-SOD323-R")
      (footprint "eagle-import:SOD323-R")
      (libsource (lib "eagle-import") (part "DIODE-SOD323-R"))
    )
    (comp (ref "J4")
      (value "M02PTH")
      (footprint "eagle-import:1X02")
      (libsource (lib "eagle-import") (part "M02PTH"))
    )
    (comp (ref "Q1")
      (value "-NPN-SOT23-EBC")
      (footprint "eagle-import:SOT23-EBC")
      (libsource (lib "eagle-import") (part "-NPN-SOT23-EBC"))
    )
    (comp (ref "R1")
      (value "100")
      (footprint "eagle-import:R0603")
      (libsource (lib "eagle-import") (part "R-US_R0603"))
    )
    (comp (ref "R2")
      (value "1k")
      (footprint "eagle-import:R0603")
      (libsource (lib "eagle-import") (part "R-US_R0603"))
    )
    (comp (ref "R3")
      (value "6.04k")
      (footprint "eagle-import:R0603")
      (libsource (lib "eagle-import") (part "R-US_R0603"))
    )
    (comp (ref "R4")
      (value "4.3k")
      (footprint "eagle-import:R0603")
      (libsource (lib "eagle-import") (part "R-US_R0603"))
    )
    (comp (ref "R5")
      (value "10k")
      (footprint "eagle-import:3223J")
      (libsource (lib "eagle-import") (part "TRIM_US-3223J"))
    )
    (comp (ref "R6")
      (value "1k")
      (footprint "eagle-import:R0603")
      (libsource (lib "eagle-import") (part "R-US_R0603"))
    )
    (comp (ref "R7")
      (value "1k")
      (footprint "eagle-import:R0603")
      (libsource (lib "eagle-import") (part "R-US_R0603"))
    )
    (comp (ref "R8")
      (value "1k")
      (footprint "eagle-import:R0603")
      (libsource (lib "eagle-import") (part "R-US_R0603"))
    )
    (comp (ref "R9")
      (value "100")
      (footprint "eagle-import:R0603")
      (libsource (lib "eagle-import") (part "R-US_R0603"))
    )
    (comp (ref "R10")
      (value "1k")
      (footprint "eagle-import:R0402")
      (libsource (lib "eagle-import") (part "R-US_R0402"))
    )
    (comp (ref "TP1")
      (value "SMD2")
      (footprint "eagle-import:SMD1,27-2,54")
      (libsource (lib "eagle-import") (part "SMD2"))
    )
    (comp (ref "U1")
      (value "A206")
      (footprint "eagle-import:SOCKET-16")
      (libsource (lib "eagle-import") (part "DIL16S"))
    )
    (comp (ref "U2")
      (value "AD847ARZ")
      (footprint "eagle-import:SO8")
      (libsource (lib "eagle-import") (part "AD847ARZ"))
    )
    (comp (ref "U3")
      (value "AD843AQ")
      (footprint "eagle-import:DIL08")
      (libsource (lib "eagle-import") (part "AD843AQ"))
    )
    (comp (ref "X1")
      (value "U.FL")
      (footprint "eagle-import:U.FL")
      (libsource (lib "eagle-import") (part "ANTENNA_U.FL"))
    )
  )
  (nets
    (net (code "1") (name "+5V") (class "Default")
      (node (ref "+5V") (pin "1") (pinfunction "P_1") (pintype "passive"))
      (node (ref "C17") (pin "1") (pinfunction "1_1") (pintype "passive"))
      (node (ref "C30") (pin "1") (pinfunction "1_1") (pintype "passive"))
      (node (ref "C4") (pin "1") (pinfunction "1_1") (pintype "passive"))
      (node (ref "C43") (pin "1") (pinfunction "1_1") (pintype "passive"))
      (node (ref "C53") (pin "1") (pinfunction "1_1") (pintype "passive"))
      (node (ref "C54") (pin "1") (pinfunction "1_1") (pintype "passive"))
      (node (ref "C55") (pin "1") (pinfunction "1_1") (pintype "passive"))
      (node (ref "C56") (pin "1") (pinfunction "1_1") (pintype "passive"))
      (node (ref "R15") (pin "1") (pinfunction "A_1") (pintype "passive"))
      (node (ref "R25") (pin "1") (pinfunction "A_1") (pintype "passive"))
      (node (ref "R35") (pin "1") (pinfunction "A_1") (pintype "passive"))
      (node (ref "R5") (pin "1") (pinfunction "A_1") (pintype "passive"))
      (node (ref "U1") (pin "11") (pinfunction "11_11") (pintype "passive"))
      (node (ref "U10") (pin "11") (pinfunction "11_11") (pintype "passive"))
      (node (ref "U13") (pin "1") (pinfunction "AVDD_1") (pintype "power_in"))
      (node (ref "U13") (pin "21") (pinfunction "DVDD_21") (pintype "power_in"))
      (node (ref "U4") (pin "11") (pinfunction "11_11") (pintype "passive"))
      (node (ref "U7") (pin "11") (pinfunction "11_11") (pintype "passive"))
      (node (ref "X5") (pin "B29") (pinfunction "+5V_B29") (pintype "passive"))
      (node (ref "X5") (pin "B3") (pinfunction "+5V_B3") (pintype "passive"))
      (node (ref "X5") (pin "D16") (pinfunction "+5V_D16") (pintype "passive"))
    )
    (net (code "2") (name "+12V") (class "Default")
      (node (ref "+12V") (pin "1") (pinfunction "P_1") (pintype "passive"))
      (node (ref "C11") (pin "1") (pinfunction "1_1") (pintype "passive"))
      (node (ref "C18") (pin "1") (pinfunction "1_1") (pintype "passive"))
      (node (ref "C19") (pin "1") (pinfunction "1_1") (pintype "passive"))
      (node (ref "C24") (pin "1") (pinfunction "1_1") (pintype "passive"))
      (node (ref "C31") (pin "1") (pinfunction "1_1") (pintype "passive"))
      (node (ref "C32") (pin "1") (pinfunction "1_1") (pintype "passive"))
      (node (ref "C37") (pin "1") (pinfunction "1_1") (pintype "passive"))
      (node (ref "C44") (pin "1") (pinfunction "1_1") (pintype "passive"))
      (node (ref "C45") (pin "1") (pinfunction "1_1") (pintype "passive"))
      (node (ref "C5") (pin "1") (pinfunction "1_1") (pintype "passive"))
      (node (ref "C50") (pin "1") (pinfunction "1_1") (pintype "passive"))
      (node (ref "C57") (pin "1") (pinfunction "1_1") (pintype "passive"))
      (node (ref "C6") (pin "1") (pinfunction "1_1") (pintype "passive"))
      (node (ref "R1") (pin "1") (pinfunction "1_1") (pintype "passive"))
      (node (ref "R11") (pin "1") (pinfunction "1_1") (pintype "passive"))
      (node (ref "R21") (pin "1") (pinfunction "1_1") (pintype "passive"))
      (node (ref "R31") (pin "1") (pinfunction "1_1") (pintype "passive"))
      (node (ref "U11") (pin "7") (pinfunction "+VS_7") (pintype "input"))
      (node (ref "U12") (pin "7") (pinfunction "+VS_7") (pintype "input"))
      (node (ref "U13") (pin "14") (pinfunction "HVDD_14") (pintype "input"))
      (node (ref "U2") (pin "7") (pinfunction "+VS_7") (pintype "input"))
      (node (ref "U3") (pin "7") (pinfunction "+VS_7") (pintype "input"))
      (node (ref "U5") (pin "7") (pinfunction "+VS_7") (pintype "input"))
      (node (ref "U6") (pin "7") (pinfunction "+VS_7") (pintype "input"))
      (node (ref "U8") (pin "7") (pinfunction "+VS_7") (pintype "input"))
      (node (ref "U9") (pin "7") (pinfunction "+VS_7") (pintype "input"))
      (node (ref "X5") (pin "B9") (pinfunction "+12V_B9") (pintype "passive"))
    )
    (net (code "3") (name "-12V") (class "Default")
      (node (ref "-12V") (pin "1") (pinfunction "P_1") (pintype "passive"))
      (node (ref "C12") (pin "1") (pinfunction "1_1") (pintype "passive"))
      (node (ref "C20") (pin "1") (pinfunction "1_1") (pintype "passive"))
      (node (ref "C21") (pin "1") (pinfunction "1_1") (pintype "passive"))
      (node (ref "C25") (pin "1") (pinfunction "1_1") (pintype "passive"))
      (node (ref "C33") (pin "1") (pinfunction "1_1") (pintype "passive"))
      (node (ref "C34") (pin "1") (pinfunction "1_1") (pintype "passive"))
      (node (ref "C38") (pin "1") (pinfunction "1_1") (pintype "passive"))
      (node (ref "C46") (pin "1") (pinfunction "1_1") (pintype "passive"))
      (node (ref "C47") (pin "1") (pinfunction "1_1") (pintype "passive"))
      (node (ref "C51") (pin "1") (pinfunction "1_1") (pintype "passive"))
      (node (ref "C7") (pin "1") (pinfunction "1_1") (pintype "passive"))
      (node (ref "C8") (pin "1") (pinfunction "1_1") (pintype "passive"))
      (node (ref "U11") (pin "4") (pinfunction "-VS_4") (pintype "input"))
      (node (ref "U12") (pin "4") (pinfunction "-VS_4") (pintype "input"))
      (node (ref "U2") (pin "4") (pinfunction "-VS_4") (pintype "input"))
      (node (ref "U3") (pin "4") (pinfunction "-VS_4") (pintype "input"))
      (node (ref "U5") (pin "4") (pinfunction "-VS_4") (pintype "input"))
      (node (ref "U6") (pin "4") (pinfunction "-VS_4") (pintype "input"))
      (node (ref "U8") (pin "4") (pinfunction "-VS_4") (pintype "input"))
      (node (ref "U9") (pin "4") (pinfunction "-VS_4") (pintype "input"))
      (node (ref "X5") (pin "B7") (pinfunction "-12V_B7") (pintype "passive"))
    )
    (net (code "4") (name "A225_OUT1") (class "Default")
      (node (ref "U1") (pin "16") (pinfunction "16_16") (pintype "passive"))
      (node (ref "X1") (pin "3") (pinfunction "SIGNAL_3") (pintype "passive"))
    )
    (net (code "5") (name "A225_OUT2") (class "Default")
      (node (ref "U4") (pin "16") (pinfunction "16_16") (pintype "passive"))
      (node (ref "X2") (pin "3") (pinfunction "SIGNAL_3") (pintype "passive"))
    )
    (net (code "6") (name "A225_OUT3") (class "Default")
      (node (ref "U7") (pin "16") (pinfunction "16_16") (pintype "passive"))
      (node (ref "X3") (pin "3") (pinfunction "SIGNAL_3") (pintype "passive"))
    )
    (net (code "7") (name "A225_OUT4") (class "Default")
      (node (ref "U10") (pin "16") (pinfunction "16_16") (pintype "passive"))
      (node (ref "X4") (pin "3") (pinfunction "SIGNAL_3") (pintype "passive"))
    )
    (net (code "8") (name "AMPOUT1") (class "Default")
      (node (ref "R2") (pin "1") (pinfunction "1_1") (pintype "passive"))
      (node (ref "U1") (pin "12") (pinfunction "12_12") (pintype "passive"))
      (node (ref "U1") (pin "13") (pinfunction "13_13") (pintype "passive"))
    )
    (net (code "9") (name "AMPOUT2") (class "Default")
      (node (ref "R12") (pin "1") (pinfunction "1_1") (pintype "passive"))
      (node (ref "U4") (pin "12") (pinfunction "12_12") (pintype "passive"))
      (node (ref "U4") (pin "13") (pinfunction "13_13") (pintype "passive"))
    )
    (net (code "10") (name "AMPOUT3") (class "Default")
      (node (ref "R22") (pin "1") (pinfunction "1_1") (pintype "passive"))
      (node (ref "U7") (pin "12") (pinfunction "12_12") (pintype "passive"))
      (node (ref "U7") (pin "13") (pinfunction "13_13") (pintype "passive"))
    )
    (net (code "11") (name "AMPOUT4") (class "Default")
      (node (ref "R32") (pin "1") (pinfunction "1_1") (pintype "passive"))
      (node (ref "U10") (pin "12") (pinfunction "12_12") (pintype "passive"))
      (node (ref "U10") (pin "13") (pinfunction "13_13") (pintype "passive"))
    )
    (net (code "12") (name "DISCRIMINATOR1") (class "Default")
      (node (ref "J4") (pin "1") (pinfunction "1_1") (pintype "passive"))
      (node (ref "R3") (pin "2") (pinfunction "2_2") (pintype "passive"))
      (node (ref "R4") (pin "2") (pinfunction "2_2") (pintype "passive"))
    )
    (net (code "13") (name "DISCRIMINATOR2") (class "Default")
      (node (ref "J5") (pin "1") (pinfunction "1_1") (pintype "passive"))
      (node (ref "R13") (pin "2") (pinfunction "2_2") (pintype "passive"))
      (node (ref "R14") (pin "2") (pinfunction "2_2") (pintype "passive"))
    )
    (net (code "14") (name "DISCRIMINATOR3") (class "Default")
      (node (ref "J6") (pin "1") (pinfunction "1_1") (pintype "passive"))
      (node (ref "R23") (pin "2") (pinfunction "2_2") (pintype "passive"))
      (node (ref "R24") (pin "2") (pinfunction "2_2") (pintype "passive"))
    )
    (net (code "15") (name "DISCRIMINATOR4") (class "Default")
      (node (ref "J7") (pin "1") (pinfunction "1_1") (pintype "passive"))
      (node (ref "R33") (pin "2") (pinfunction "2_2") (pintype "passive"))
      (node (ref "R34") (pin "2") (pinfunction "2_2") (pintype "passive"))
    )
    (net (code "16") (name "GND") (class "Default")
      (node (ref "C1") (pin "-") (pinfunction "-_-") (pintype "passive"))
      (node (ref "C11") (pin "2") (pinfunction "2_2") (pintype "passive"))
      (node (ref "C12") (pin "2") (pinfunction "2_2") (pintype "passive"))
      (node (ref "C13") (pin "2") (pinfunction "2_2") (pintype "passive"))
      (node (ref "C14") (pin "-") (pinfunction "-_-") (pintype "passive"))
      (node (ref "C15") (pin "2") (pinfunction "2_2") (pintype "passive"))
      (node (ref "C16") (pin "2") (pinfunction "2_2") (pintype "passive"))
      (node (ref "C17") (pin "2") (pinfunction "2_2") (pintype "passive"))
      (node (ref "C18") (pin "2") (pinfunction "2_2") (pintype "passive"))
      (node (ref "C19") (pin "2") (pinfunction "2_2") (pintype "passive"))
      (node (ref "C2") (pin "2") (pinfunction "2_2") (pintype "passive"))
      (node (ref "C20") (pin "2") (pinfunction "2_2") (pintype "passive"))
      (node (ref "C21") (pin "2") (pinfunction "2_2") (pintype "passive"))
      (node (ref "C22") (pin "2") (pinfunction "2_2") (pintype "passive"))
      (node (ref "C24") (pin "2") (pinfunction "2_2") (pintype "passive"))
      (node (ref "C25") (pin "2") (pinfunction "2_2") (pintype "passive"))
      (node (ref "C26") (pin "2") (pinfunction "2_2") (pintype "passive"))
      (node (ref "C27") (pin "-") (pinfunction "-_-") (pintype "passive"))
      (node (ref "C28") (pin "2") (pinfunction "2_2") (pintype "passive"))
      (node (ref "C29") (pin "2") (pinfunction "2_2") (pintype "passive"))
      (node (ref "C3") (pin "2") (pinfunction "2_2") (pintype "passive"))
      (node (ref "C30") (pin "2") (pinfunction "2_2") (pintype "passive"))
      (node (ref "C31") (pin "2") (pinfunction "2_2") (pintype "passive"))
      (node (ref "C32") (pin "2") (pinfunction "2_2") (pintype "passive"))
      (node (ref "C33") (pin "2") (pinfunction "2_2") (pintype "passive"))
      (node (ref "C34") (pin "2") (pinfunction "2_2") (pintype "passive"))
      (node (ref "C35") (pin "2") (pinfunction "2_2") (pintype "passive"))
      (node (ref "C37") (pin "2") (pinfunction "2_2") (pintype "passive"))
      (node (ref "C38") (pin "2") (pinfunction "2_2") (pintype "passive"))
      (node (ref "C39") (pin "2") (pinfunction "2_2") (pintype "passive"))
      (node (ref "C4") (pin "2") (pinfunction "2_2") (pintype "passive"))
      (node (ref "C40") (pin "-") (pinfunction "-_-") (pintype "passive"))
      (node (ref "C41") (pin "2") (pinfunction "2_2") (pintype "passive"))
      (node (ref "C42") (pin "2") (pinfunction "2_2") (pintype "passive"))
      (node (ref "C43") (pin "2") (pinfunction "2_2") (pintype "passive"))
      (node (ref "C44") (pin "2") (pinfunction "2_2") (pintype "passive"))
      (node (ref "C45") (pin "2") (pinfunction "2_2") (pintype "passive"))
      (node (ref "C46") (pin "2") (pinfunction "2_2") (pintype "passive"))
      (node (ref "C47") (pin "2") (pinfunction "2_2") (pintype "passive"))
      (node (ref "C48") (pin "2") (pinfunction "2_2") (pintype "passive"))
      (node (ref "C5") (pin "2") (pinfunction "2_2") (pintype "passive"))
      (node (ref "C50") (pin "2") (pinfunction "2_2") (pintype "passive"))
      (node (ref "C51") (pin "2") (pinfunction "2_2") (pintype "passive"))
      (node (ref "C52") (pin "2") (pinfunction "2_2") (pintype "passive"))
      (node (ref "C53") (pin "2") (pinfunction "2_2") (pintype "passive"))
      (node (ref "C54") (pin "2") (pinfunction "2_2") (pintype "passive"))
      (node (ref "C55") (pin "2") (pinfunction "2_2") (pintype "passive"))
      (node (ref "C56") (pin "2") (pinfunction "2_2") (pintype "passive"))
      (node (ref "C57") (pin "2") (pinfunction "2_2") (pintype "passive"))
      (node (ref "C58") (pin "2") (pinfunction "2_2") (pintype "passive"))
      (node (ref "C6") (pin "2") (pinfunction "2_2") (pintype "passive"))
      (node (ref "C7") (pin "2") (pinfunction "2_2") (pintype "passive"))
      (node (ref "C8") (pin "2") (pinfunction "2_2") (pintype "passive"))
      (node (ref "C9") (pin "2") (pinfunction "2_2") (pintype "passive"))
      (node (ref "D1") (pin "1") (pinfunction "A_1") (pintype "passive"))
      (node (ref "D10") (pin "1") (pinfunction "A_1") (pintype "passive"))
      (node (ref "D4") (pin "1") (pinfunction "A_1") (pintype "passive"))
      (node (ref "D7") (pin "1") (pinfunction "A_1") (pintype "passive"))
      (node (ref "GND") (pin "1") (pinfunction "P_1") (pintype "passive"))
      (node (ref "J3") (pin "4") (pinfunction "4_4") (pintype "passive"))
      (node (ref "Q1") (pin "E") (pinfunction "E_E") (pintype "passive"))
      (node (ref "Q2") (pin "E") (pinfunction "E_E") (pintype "passive"))
      (node (ref "Q3") (pin "E") (pinfunction "E_E") (pintype "passive"))
      (node (ref "Q4") (pin "E") (pinfunction "E_E") (pintype "passive"))
      (node (ref "R14") (pin "1") (pinfunction "1_1") (pintype "passive"))
      (node (ref "R15") (pin "3") (pinfunction "E_3") (pintype "passive"))
      (node (ref "R19") (pin "1") (pinfunction "1_1") (pintype "passive"))
      (node (ref "R24") (pin "1") (pinfunction "1_1") (pintype "passive"))
      (node (ref "R25") (pin "3") (pinfunction "E_3") (pintype "passive"))
      (node (ref "R29") (pin "1") (pinfunction "1_1") (pintype "passive"))
      (node (ref "R34") (pin "1") (pinfunction "1_1") (pintype "passive"))
      (node (ref "R35") (pin "3") (pinfunction "E_3") (pintype "passive"))
      (node (ref "R39") (pin "1") (pinfunction "1_1") (pintype "passive"))
      (node (ref "R4") (pin "1") (pinfunction "1_1") (pintype "passive"))
      (node (ref "R5") (pin "3") (pinfunction "E_3") (pintype "passive"))
      (node (ref "R9") (pin "1") (pinfunction "1_1") (pintype "passive"))
      (node (ref "SJ1") (pin "1") (pinfunction "1_1") (pintype "passive"))
      (node (ref "SJ2") (pin "1") (pinfunction "1_1") (pintype "passive"))
      (node (ref "SJ3") (pin "1") (pinfunction "1_1") (pintype "passive"))
      (node (ref "SJ4") (pin "1") (pinfunction "1_1") (pintype "passive"))
      (node (ref "U1") (pin "1") (pinfunction "1_1") (pintype "passive"))
      (node (ref "U1") (pin "14") (pinfunction "14_14") (pintype "passive"))
      (node (ref "U1") (pin "15") (pinfunction "15_15") (pintype "passive"))
      (node (ref "U1") (pin "2") (pinfunction "2_2") (pintype "passive"))
      (node (ref "U1") (pin "7") (pinfunction "7_7") (pintype "passive"))
      (node (ref "U10") (pin "1") (pinfunction "1_1") (pintype "passive"))
      (node (ref "U10") (pin "14") (pinfunction "14_14") (pintype "passive"))
      (node (ref "U10") (pin "15") (pinfunction "15_15") (pintype "passive"))
      (node (ref "U10") (pin "2") (pinfunction "2_2") (pintype "passive"))
      (node (ref "U10") (pin "7") (pinfunction "7_7") (pintype "passive"))
      (node (ref "U13") (pin "15") (pinfunction "HVSS_15") (pintype "input"))
      (node (ref "U13") (pin "2") (pinfunction "AGND1_2") (pintype "power_in"))
      (node (ref "U13") (pin "20") (pinfunction "DGND_20") (pintype "power_in"))
      (node (ref "U13") (pin "23") (pinfunction "REFGND_23") (pintype "input"))
      (node (ref "U13") (pin "3") (pinfunction "AGND2_3") (pintype "power_in"))
      (node (ref "U13") (pin "5") (pinfunction "AINGND_5") (pintype "input"))
      (node (ref "U13") (pin "EP") (pinfunction "PAD_EP") (pintype "power_in"))
      (node (ref "U4") (pin "1") (pinfunction "1_1") (pintype "passive"))
      (node (ref "U4") (pin "14") (pinfunction "14_14") (pintype "passive"))
      (node (ref "U4") (pin "15") (pinfunction "15_15") (pintype "passive"))
      (node (ref "U4") (pin "2") (pinfunction "2_2") (pintype "passive"))
      (node (ref "U4") (pin "7") (pinfunction "7_7") (pintype "passive"))
      (node (ref "U7") (pin "1") (pinfunction "1_1") (pintype "passive"))
      (node (ref "U7") (pin "14") (pinfunction "14_14") (pintype "passive"))
      (node (ref "U7") (pin "15") (pinfunction "15_15") (pintype "passive"))
      (node (ref "U7") (pin "2") (pinfunction "2_2") (pintype "passive"))
      (node (ref "U7") (pin "7") (pinfunction "7_7") (pintype "passive"))
      (node (ref "X1") (pin "1") (pinfunction "GND_1") (pintype "passive"))
      (node (ref "X1") (pin "2") (pinfunction "GND_2") (pintype "passive"))
      (node (ref "X2") (pin "1") (pinfunction "GND_1") (pintype "passive"))
      (node (ref "X2") (pin "2") (pinfunction "GND_2") (pintype "passive"))
      (node (ref "X3") (pin "1") (pinfunction "GND_1") (pintype "passive"))
      (node (ref "X3") (pin "2") (pinfunction "GND_2") (pintype "passive"))
      (node (ref "X4") (pin "1") (pinfunction "GND_1") (pintype "passive"))
      (node (ref "X4") (pin "2") (pinfunction "GND_2") (pintype "passive"))
      (node (ref "X5") (pin "A32") (pinfunction "0V_A32") (pintype "passive"))
      (node (ref "X5") (pin "B1") (pinfunction "0V_B1") (pintype "passive"))
      (node (ref "X5") (pin "B31") (pinfunction "0V_B31") (pintype "passive"))
      (node (ref "X5") (pin "B32") (pinfunction "0V_B32") (pintype "passive"))
      (node (ref "X5") (pin "C0") (pinfunction "0V_C0") (pintype "passive"))
      (node (ref "X5") (pin "D0") (pinfunction "0V_D0") (pintype "passive"))
      (node (ref "X5") (pin "D18") (pinfunction "0V_D18") (pintype "passive"))
      (node (ref "X5") (pin "D19") (pinfunction "0V_D19") (pintype "passive"))
    )
    (net (code "17") (name "Net-(C1-Pad+)") (class "Default")
      (node (ref "C1") (pin "+") (pinfunction "+_+") (pintype "passive"))
      (node (ref "C2") (pin "1") (pinfunction "1_1") (pintype "passive"))
      (node (ref "R1") (pin "2") (pinfunction "2_2") (pintype "passive"))
      (node (ref "U1") (pin "4") (pinfunction "4_4") (pintype "passive"))
      (node (ref "U1") (pin "5") (pinfunction "5_5") (pintype "passive"))
    )
    (net (code "18") (name "Net-(C10-Pad2)") (class "Default")
      (node (ref "C10") (pin "2") (pinfunction "2_2") (pintype "passive"))
      (node (ref "R9") (pin "2") (pinfunction "2_2") (pintype "passive"))
    )
    (net (code "19") (name "Net-(C14-Pad+)") (class "Default")
      (node (ref "C14") (pin "+") (pinfunction "+_+") (pintype "passive"))
      (node (ref "C15") (pin "1") (pinfunction "1_1") (pintype "passive"))
      (node (ref "R11") (pin "2") (pinfunction "2_2") (pintype "passive"))
      (node (ref "U4") (pin "4") (pinfunction "4_4") (pintype "passive"))
      (node (ref "U4") (pin "5") (pinfunction "5_5") (pintype "passive"))
    )
    (net (code "20") (name "Net-(C23-Pad2)") (class "Default")
      (node (ref "C23") (pin "2") (pinfunction "2_2") (pintype "passive"))
      (node (ref "R19") (pin "2") (pinfunction "2_2") (pintype "passive"))
    )
    (net (code "21") (name "Net-(C27-Pad+)") (class "Default")
      (node (ref "C27") (pin "+") (pinfunction "+_+") (pintype "passive"))
      (node (ref "C28") (pin "1") (pinfunction "1_1") (pintype "passive"))
      (node (ref "R21") (pin "2") (pinfunction "2_2") (pintype "passive"))
      (node (ref "U7") (pin "4") (pinfunction "4_4") (pintype "passive"))
      (node (ref "U7") (pin "5") (pinfunction "5_5") (pintype "passive"))
    )
    (net (code "22") (name "Net-(C36-Pad2)") (class "Default")
      (node (ref "C36") (pin "2") (pinfunction "2_2") (pintype "passive"))
      (node (ref "R29") (pin "2") (pinfunction "2_2") (pintype "passive"))
    )
    (net (code "23") (name "Net-(C40-Pad+)") (class "Default")
      (node (ref "C40") (pin "+") (pinfunction "+_+") (pintype "passive"))
      (node (ref "C41") (pin "1") (pinfunction "1_1") (pintype "passive"))
      (node (ref "R31") (pin "2") (pinfunction "2_2") (pintype "passive"))
      (node (ref "U10") (pin "4") (pinfunction "4_4") (pintype "passive"))
      (node (ref "U10") (pin "5") (pinfunction "5_5") (pintype "passive"))
    )
    (net (code "24") (name "Net-(C49-Pad2)") (class "Default")
      (node (ref "C49") (pin "2") (pinfunction "2_2") (pintype "passive"))
      (node (ref "R39") (pin "2") (pinfunction "2_2") (pintype "passive"))
    )
    (net (code "25") (name "Net-(D1-C)") (class "Default")
      (node (ref "C3") (pin "1") (pinfunction "1_1") (pintype "passive"))
      (node (ref "D1") (pin "3") (pinfunction "C_3") (pintype "passive"))
      (node (ref "R2") (pin "2") (pinfunction "2_2") (pintype "passive"))
      (node (ref "TP1") (pin "1") (pinfunction "P_1") (pintype "passive"))
      (node (ref "U2") (pin "3") (pinfunction "IN+_3") (pintype "input"))
    )
    (net (code "26") (name "Net-(D4-C)") (class "Default")
      (node (ref "C16") (pin "1") (pinfunction "1_1") (pintype "passive"))
      (node (ref "D4") (pin "3") (pinfunction "C_3") (pintype "passive"))
      (node (ref "R12") (pin "2") (pinfunction "2_2") (pintype "passive"))
      (node (ref "TP2") (pin "1") (pinfunction "P_1") (pintype "passive"))
      (node (ref "U5") (pin "3") (pinfunction "IN+_3") (pintype "input"))
    )
    (net (code "27") (name "Net-(D7-C)") (class "Default")
      (node (ref "C29") (pin "1") (pinfunction "1_1") (pintype "passive"))
      (node (ref "D7") (pin "3") (pinfunction "C_3") (pintype "passive"))
      (node (ref "R22") (pin "2") (pinfunction "2_2") (pintype "passive"))
      (node (ref "TP3") (pin "1") (pinfunction "P_1") (pintype "passive"))
      (node (ref "U8") (pin "3") (pinfunction "IN+_3") (pintype "input"))
    )
    (net (code "28") (name "Net-(D10-C)") (class "Default")
      (node (ref "C42") (pin "1") (pinfunction "1_1") (pintype "passive"))
      (node (ref "D10") (pin "3") (pinfunction "C_3") (pintype "passive"))
      (node (ref "R32") (pin "2") (pinfunction "2_2") (pintype "passive"))
      (node (ref "TP4") (pin "1") (pinfunction "P_1") (pintype "passive"))
      (node (ref "U11") (pin "3") (pinfunction "IN+_3") (pintype "input"))
    )
    (net (code "29") (name "Net-(J3-Pad5)") (class "Default")
      (node (ref "J3") (pin "5") (pinfunction "5_5") (pintype "passive"))
      (node (ref "R41") (pin "2") (pinfunction "2_2") (pintype "passive"))
    )
    (net (code "30") (name "Net-(Q1-PadB)") (class "Default")
      (node (ref "Q1") (pin "B") (pinfunction "B_B") (pintype "passive"))
      (node (ref "R7") (pin "2") (pinfunction "2_2") (pintype "passive"))
    )
    (net (code "31") (name "Net-(Q2-PadB)") (class "Default")
      (node (ref "Q2") (pin "B") (pinfunction "B_B") (pintype "passive"))
      (node (ref "R17") (pin "2") (pinfunction "2_2") (pintype "passive"))
    )
    (net (code "32") (name "Net-(Q3-PadB)") (class "Default")
      (node (ref "Q3") (pin "B") (pinfunction "B_B") (pintype "passive"))
      (node (ref "R27") (pin "2") (pinfunction "2_2") (pintype "passive"))
    )
    (net (code "33") (name "Net-(Q4-PadB)") (class "Default")
      (node (ref "Q4") (pin "B") (pinfunction "B_B") (pintype "passive"))
      (node (ref "R37") (pin "2") (pinfunction "2_2") (pintype "passive"))
    )
    (net (code "34") (name "Net-(R3-Pad1)") (class "Default")
      (node (ref "R3") (pin "1") (pinfunction "1_1") (pintype "passive"))
      (node (ref "U1") (pin "9") (pinfunction "9_9") (pintype "passive"))
    )
    (net (code "35") (name "Net-(R5-S)") (class "Default")
      (node (ref "R5") (pin "2") (pinfunction "S_2") (pintype "passive"))
      (node (ref "R6") (pin "2") (pinfunction "2_2") (pintype "passive"))
    )
    (net (code "36") (name "Net-(R13-Pad1)") (class "Default")
      (node (ref "R13") (pin "1") (pinfunction "1_1") (pintype "passive"))
      (node (ref "U4") (pin "9") (pinfunction "9_9") (pintype "passive"))
    )
    (net (code "37") (name "Net-(R15-S)") (class "Default")
      (node (ref "R15") (pin "2") (pinfunction "S_2") (pintype "passive"))
      (node (ref "R16") (pin "2") (pinfunction "2_2") (pintype "passive"))
    )
    (net (code "38") (name "Net-(R23-Pad1)") (class "Default")
      (node (ref "R23") (pin "1") (pinfunction "1_1") (pintype "passive"))
      (node (ref "U7") (pin "9") (pinfunction "9_9") (pintype "passive"))
    )
    (net (code "39") (name "Net-(R25-S)") (class "Default")
      (node (ref "R25") (pin "2") (pinfunction "S_2") (pintype "passive"))
      (node (ref "R26") (pin "2") (pinfunction "2_2") (pintype "passive"))
    )
    (net (code "40") (name "Net-(R33-Pad1)") (class "Default")
      (node (ref "R33") (pin "1") (pinfunction "1_1") (pintype "passive"))
      (node (ref "U10") (pin "9") (pinfunction "9_9") (pintype "passive"))
    )
    (net (code "41") (name "Net-(R35-S)") (class "Default")
      (node (ref "R35") (pin "2") (pinfunction "S_2") (pintype "passive"))
      (node (ref "R36") (pin "2") (pinfunction "2_2") (pintype "passive"))
    )
    (net (code "42") (name "Net-(U2-IN-)") (class "Default")
      (node (ref "D2") (pin "A") (pinfunction "A_A") (pintype "passive"))
      (node (ref "R8") (pin "1") (pinfunction "1_1") (pintype "passive"))
      (node (ref "U2") (pin "2") (pinfunction "IN-_2") (pintype "input"))
    )
    (net (code "43") (name "Net-(U2-OUT)") (class "Default")
      (node (ref "D2") (pin "C") (pinfunction "C_C") (pintype "passive"))
      (node (ref "D3") (pin "A") (pinfunction "A_A") (pintype "passive"))
      (node (ref "U2") (pin "6") (pinfunction "OUT_6") (pintype "output"))
    )
    (net (code "44") (name "Net-(U3-IN+)") (class "Default")
      (node (ref "C10") (pin "1") (pinfunction "1_1") (pintype "passive"))
      (node (ref "D3") (pin "C") (pinfunction "C_C") (pintype "passive"))
      (node (ref "Q1") (pin "C") (pinfunction "C_C") (pintype "passive"))
      (node (ref "U3") (pin "3") (pinfunction "IN+_3") (pintype "input"))
    )
    (net (code "45") (name "Net-(U3-IN-)") (class "Default")
      (node (ref "R10") (pin "1") (pinfunction "1_1") (pintype "passive"))
      (node (ref "R8") (pin "2") (pinfunction "2_2") (pintype "passive"))
      (node (ref "U3") (pin "2") (pinfunction "IN-_2") (pintype "input"))
      (node (ref "U3") (pin "6") (pinfunction "OUT_6") (pintype "output"))
    )
    (net (code "46") (name "Net-(U5-IN-)") (class "Default")
      (node (ref "D5") (pin "A") (pinfunction "A_A") (pintype "passive"))
      (node (ref "R18") (pin "1") (pinfunction "1_1") (pintype "passive"))
      (node (ref "U5") (pin "2") (pinfunction "IN-_2") (pintype "input"))
    )
    (net (code "47") (name "Net-(U5-OUT)") (class "Default")
      (node (ref "D5") (pin "C") (pinfunction "C_C") (pintype "passive"))
      (node (ref "D6") (pin "A") (pinfunction "A_A") (pintype "passive"))
      (node (ref "U5") (pin "6") (pinfunction "OUT_6") (pintype "output"))
    )
    (net (code "48") (name "Net-(U6-IN+)") (class "Default")
      (node (ref "C23") (pin "1") (pinfunction "1_1") (pintype "passive"))
      (node (ref "D6") (pin "C") (pinfunction "C_C") (pintype "passive"))
      (node (ref "Q2") (pin "C") (pinfunction "C_C") (pintype "passive"))
      (node (ref "U6") (pin "3") (pinfunction "IN+_3") (pintype "input"))
    )
    (net (code "49") (name "Net-(U6-IN-)") (class "Default")
      (node (ref "R18") (pin "2") (pinfunction "2_2") (pintype "passive"))
      (node (ref "R20") (pin "1") (pinfunction "1_1") (pintype "passive"))
      (node (ref "U6") (pin "2") (pinfunction "IN-_2") (pintype "input"))
      (node (ref "U6") (pin "6") (pinfunction "OUT_6") (pintype "output"))
    )
    (net (code "50") (name "Net-(U8-IN-)") (class "Default")
      (node (ref "D8") (pin "A") (pinfunction "A_A") (pintype "passive"))
      (node (ref "R28") (pin "1") (pinfunction "1_1") (pintype "passive"))
      (node (ref "U8") (pin "2") (pinfunction "IN-_2") (pintype "input"))
    )
    (net (code "51") (name "Net-(U8-OUT)") (class "Default")
      (node (ref "D8") (pin "C") (pinfunction "C_C") (pintype "passive"))
      (node (ref "D9") (pin "A") (pinfunction "A_A") (pintype "passive"))
      (node (ref "U8") (pin "6") (pinfunction "OUT_6") (pintype "output"))
    )
    (net (code "52") (name "Net-(U9-IN+)") (class "Default")
      (node (ref "C36") (pin "1") (pinfunction "1_1") (pintype "passive"))
      (node (ref "D9") (pin "C") (pinfunction "C_C") (pintype "passive"))
      (node (ref "Q3") (pin "C") (pinfunction "C_C") (pintype "passive"))
      (node (ref "U9") (pin "3") (pinfunction "IN+_3") (pintype "input"))
    )
    (net (code "53") (name "Net-(U9-IN-)") (class "Default")
      (node (ref "R28") (pin "2") (pinfunction "2_2") (pintype "passive"))
      (node (ref "R30") (pin "1") (pinfunction "1_1") (pintype "passive"))
      (node (ref "U9") (pin "2") (pinfunction "IN-_2") (pintype "input"))
      (node (ref "U9") (pin "6") (pinfunction "OUT_6") (pintype "output"))
    )
    (net (code "54") (name "Net-(U11-IN-)") (class "Default")
      (node (ref "D11") (pin "A") (pinfunction "A_A") (pintype "passive"))
      (node (ref "R38") (pin "1") (pinfunction "1_1") (pintype "passive"))
      (node (ref "U11") (pin "2") (pinfunction "IN-_2") (pintype "input"))
    )
    (net (code "55") (name "Net-(U11-OUT)") (class "Default")
      (node (ref "D11") (pin "C") (pinfunction "C_C") (pintype "passive"))
      (node (ref "D12") (pin "A") (pinfunction "A_A") (pintype "passive"))
      (node (ref "U11") (pin "6") (pinfunction "OUT_6") (pintype "output"))
    )
    (net (code "56") (name "Net-(U12-IN+)") (class "Default")
      (node (ref "C49") (pin "1") (pinfunction "1_1") (pintype "passive"))
      (node (ref "D12") (pin "C") (pinfunction "C_C") (pintype "passive"))
      (node (ref "Q4") (pin "C") (pinfunction "C_C") (pintype "passive"))
      (node (ref "U12") (pin "3") (pinfunction "IN+_3") (pintype "input"))
    )
    (net (code "57") (name "Net-(U12-IN-)") (class "Default")
      (node (ref "R38") (pin "2") (pinfunction "2_2") (pintype "passive"))
      (node (ref "R40") (pin "1") (pinfunction "1_1") (pintype "passive"))
      (node (ref "U12") (pin "2") (pinfunction "IN-_2") (pintype "input"))
      (node (ref "U12") (pin "6") (pinfunction "OUT_6") (pintype "output"))
    )
    (net (code "58") (name "Net-(U13-AL_PD)") (class "Default")
      (node (ref "J3") (pin "2") (pinfunction "2_2") (pintype "passive"))
      (node (ref "U13") (pin "22") (pinfunction "AL_PD_22") (pintype "bidirectional"))
    )
    (net (code "59") (name "Net-(U13-CS)") (class "Default")
      (node (ref "J3") (pin "1") (pinfunction "1_1") (pintype "passive"))
      (node (ref "U13") (pin "16") (pinfunction "CS_16") (pintype "input"))
    )
    (net (code "60") (name "Net-(U13-DIN)") (class "Default")
      (node (ref "J3") (pin "6") (pinfunction "6_6") (pintype "passive"))
      (node (ref "U13") (pin "18") (pinfunction "DIN_18") (pintype "input"))
    )
    (net (code "61") (name "Net-(U13-DOUT)") (class "Default")
      (node (ref "R41") (pin "1") (pinfunction "1_1") (pintype "passive"))
      (node (ref "U13") (pin "19") (pinfunction "DOUT_19") (pintype "output"))
    )
    (net (code "62") (name "Net-(U13-REF)") (class "Default")
      (node (ref "C58") (pin "1") (pinfunction "1_1") (pintype "passive"))
      (node (ref "U13") (pin "24") (pinfunction "REF_24") (pintype "input"))
    )
    (net (code "63") (name "Net-(U13-SCLK)") (class "Default")
      (node (ref "J3") (pin "3") (pinfunction "3_3") (pintype "passive"))
      (node (ref "U13") (pin "17") (pinfunction "SCLK_17") (pintype "input"))
    )
    (net (code "64") (name "Net-(X5C-1)") (class "Default")
      (node (ref "SJ1") (pin "2") (pinfunction "2_2") (pintype "passive"))
      (node (ref "X5") (pin "GND@1") (pinfunction "1_GND@1") (pintype "passive"))
    )
    (net (code "65") (name "Net-(X5D-1)") (class "Default")
      (node (ref "SJ2") (pin "2") (pinfunction "2_2") (pintype "passive"))
      (node (ref "X5") (pin "GND@2") (pinfunction "1_GND@2") (pintype "passive"))
    )
    (net (code "66") (name "Net-(X5E-1)") (class "Default")
      (node (ref "SJ3") (pin "2") (pinfunction "2_2") (pintype "passive"))
      (node (ref "X5") (pin "GND@3") (pinfunction "1_GND@3") (pintype "passive"))
    )
    (net (code "67") (name "Net-(X5F-1)") (class "Default")
      (node (ref "SJ4") (pin "2") (pinfunction "2_2") (pintype "passive"))
      (node (ref "X5") (pin "GND@4") (pinfunction "1_GND@4") (pintype "passive"))
    )
    (net (code "68") (name "PEAK1") (class "Default")
      (node (ref "C13") (pin "1") (pinfunction "1_1") (pintype "passive"))
      (node (ref "R10") (pin "2") (pinfunction "2_2") (pintype "passive"))
      (node (ref "U13") (pin "9") (pinfunction "AIN2_9") (pintype "input"))
    )
    (net (code "69") (name "PEAK2") (class "Default")
      (node (ref "C26") (pin "1") (pinfunction "1_1") (pintype "passive"))
      (node (ref "R20") (pin "2") (pinfunction "2_2") (pintype "passive"))
      (node (ref "U13") (pin "8") (pinfunction "AIN3_8") (pintype "input"))
    )
    (net (code "70") (name "PEAK3") (class "Default")
      (node (ref "C39") (pin "1") (pinfunction "1_1") (pintype "passive"))
      (node (ref "R30") (pin "2") (pinfunction "2_2") (pintype "passive"))
      (node (ref "U13") (pin "11") (pinfunction "AIN0_11") (pintype "input"))
    )
    (net (code "71") (name "PEAK4") (class "Default")
      (node (ref "C52") (pin "1") (pinfunction "1_1") (pintype "passive"))
      (node (ref "R40") (pin "2") (pinfunction "2_2") (pintype "passive"))
      (node (ref "U13") (pin "10") (pinfunction "AIN1_10") (pintype "input"))
    )
    (net (code "72") (name "RESET1") (class "Default")
      (node (ref "J4") (pin "2") (pinfunction "2_2") (pintype "passive"))
      (node (ref "R7") (pin "1") (pinfunction "1_1") (pintype "passive"))
    )
    (net (code "73") (name "RESET2") (class "Default")
      (node (ref "J5") (pin "2") (pinfunction "2_2") (pintype "passive"))
      (node (ref "R17") (pin "1") (pinfunction "1_1") (pintype "passive"))
    )
    (net (code "74") (name "RESET3") (class "Default")
      (node (ref "J6") (pin "2") (pinfunction "2_2") (pintype "passive"))
      (node (ref "R27") (pin "1") (pinfunction "1_1") (pintype "passive"))
    )
    (net (code "75") (name "RESET4") (class "Default")
      (node (ref "J7") (pin "2") (pinfunction "2_2") (pintype "passive"))
      (node (ref "R37") (pin "1") (pinfunction "1_1") (pintype "passive"))
    )
    (net (code "76") (name "VV1") (class "Default")
      (node (ref "C9") (pin "1") (pinfunction "1_1") (pintype "passive"))
      (node (ref "R6") (pin "1") (pinfunction "1_1") (pintype "passive"))
      (node (ref "U1") (pin "10") (pinfunction "10_10") (pintype "passive"))
    )
    (net (code "77") (name "VV2") (class "Default")
      (node (ref "C22") (pin "1") (pinfunction "1_1") (pintype "passive"))
      (node (ref "R16") (pin "1") (pinfunction "1_1") (pintype "passive"))
      (node (ref "U4") (pin "10") (pinfunction "10_10") (pintype "passive"))
    )
    (net (code "78") (name "VV3") (class "Default")
      (node (ref "C35") (pin "1") (pinfunction "1_1") (pintype "passive"))
      (node (ref "R26") (pin "1") (pinfunction "1_1") (pintype "passive"))
      (node (ref "U7") (pin "10") (pinfunction "10_10") (pintype "passive"))
    )
    (net (code "79") (name "VV4") (class "Default")
      (node (ref "C48") (pin "1") (pinfunction "1_1") (pintype "passive"))
      (node (ref "R36") (pin "1") (pinfunction "1_1") (pintype "passive"))
      (node (ref "U10") (pin "10") (pinfunction "10_10") (pintype "passive"))
    )
    (net (code "80") (name "unconnected-(U1-Pad3)") (class "Default")
      (node (ref "U1") (pin "3") (pinfunction "3_3") (pintype "passive"))
    )
    (net (code "81") (name "unconnected-(U1-Pad6)") (class "Default")
      (node (ref "U1") (pin "6") (pinfunction "6_6") (pintype "passive"))
    )
    (net (code "82") (name "unconnected-(U1-Pad8)") (class "Default")
      (node (ref "U1") (pin "8") (pinfunction "8_8") (pintype "passive"))
    )
    (net (code "83") (name "unconnected-(U2-OFF-Pad1)") (class "Default")
      (node (ref "U2") (pin "1") (pinfunction "OFF_1") (pintype "passive"))
    )
    (net (code "84") (name "unconnected-(U2-OFF-Pad8)") (class "Default")
      (node (ref "U2") (pin "8") (pinfunction "OFF_8") (pintype "passive"))
    )
    (net (code "85") (name "unconnected-(U3-OFF-Pad1)") (class "Default")
      (node (ref "U3") (pin "1") (pinfunction "OFF_1") (pintype "passive"))
    )
    (net (code "86") (name "unconnected-(U3-OFF-Pad8)") (class "Default")
      (node (ref "U3") (pin "8") (pinfunction "OFF_8") (pintype "passive"))
    )
    (net (code "87") (name "unconnected-(U4-Pad3)") (class "Default")
      (node (ref "U4") (pin "3") (pinfunction "3_3") (pintype "passive"))
    )
    (net (code "88") (name "unconnected-(U4-Pad6)") (class "Default")
      (node (ref "U4") (pin "6") (pinfunction "6_6") (pintype "passive"))
    )
    (net (code "89") (name "unconnected-(U4-Pad8)") (class "Default")
      (node (ref "U4") (pin "8") (pinfunction "8_8") (pintype "passive"))
    )
    (net (code "90") (name "unconnected-(U5-OFF-Pad1)") (class "Default")
      (node (ref "U5") (pin "1") (pinfunction "OFF_1") (pintype "passive"))
    )
    (net (code "91") (name "unconnected-(U5-OFF-Pad8)") (class "Default")
      (node (ref "U5") (pin "8") (pinfunction "OFF_8") (pintype "passive"))
    )
    (net (code "92") (name "unconnected-(U6-OFF-Pad1)") (class "Default")
      (node (ref "U6") (pin "1") (pinfunction "OFF_1") (pintype "passive"))
    )
    (net (code "93") (name "unconnected-(U6-OFF-Pad8)") (class "Default")
      (node (ref "U6") (pin "8") (pinfunction "OFF_8") (pintype "passive"))
    )
    (net (code "94") (name "unconnected-(U7-Pad3)") (class "Default")
      (node (ref "U7") (pin "3") (pinfunction "3_3") (pintype "passive"))
    )
    (net (code "95") (name "unconnected-(U7-Pad6)") (class "Default")
      (node (ref "U7") (pin "6") (pinfunction "6_6") (pintype "passive"))
    )
    (net (code "96") (name "unconnected-(U7-Pad8)") (class "Default")
      (node (ref "U7") (pin "8") (pinfunction "8_8") (pintype "passive"))
    )
    (net (code "97") (name "unconnected-(U8-OFF-Pad1)") (class "Default")
      (node (ref "U8") (pin "1") (pinfunction "OFF_1") (pintype "passive"))
    )
    (net (code "98") (name "unconnected-(U8-OFF-Pad8)") (class "Default")
      (node (ref "U8") (pin "8") (pinfunction "OFF_8") (pintype "passive"))
    )
    (net (code "99") (name "unconnected-(U9-OFF-Pad1)") (class "Default")
      (node (ref "U9") (pin "1") (pinfunction "OFF_1") (pintype "passive"))
    )
    (net (code "100") (name "unconnected-(U9-OFF-Pad8)") (class "Default")
      (node (ref "U9") (pin "8") (pinfunction "OFF_8") (pintype "passive"))
    )
    (net (code "101") (name "unconnected-(U10-Pad3)") (class "Default")
      (node (ref "U10") (pin "3") (pinfunction "3_3") (pintype "passive"))
    )
    (net (code "102") (name "unconnected-(U10-Pad6)") (class "Default")
      (node (ref "U10") (pin "6") (pinfunction "6_6") (pintype "passive"))
    )
    (net (code "103") (name "unconnected-(U10-Pad8)") (class "Default")
      (node (ref "U10") (pin "8") (pinfunction "8_8") (pintype "passive"))
    )
    (net (code "104") (name "unconnected-(U11-OFF-Pad1)") (class "Default")
      (node (ref "U11") (pin "1") (pinfunction "OFF_1") (pintype "passive"))
    )
    (net (code "105") (name "unconnected-(U11-OFF-Pad8)") (class "Default")
      (node (ref "U11") (pin "8") (pinfunction "OFF_8") (pintype "passive"))
    )
    (net (code "106") (name "unconnected-(U12-OFF-Pad1)") (class "Default")
      (node (ref "U12") (pin "1") (pinfunction "OFF_1") (pintype "passive"))
    )
    (net (code "107") (name "unconnected-(U12-OFF-Pad8)") (class "Default")
      (node (ref "U12") (pin "8") (pinfunction "OFF_8") (pintype "passive"))
    )
    (net (code "108") (name "unconnected-(X5A--5V-PadB5)") (class "Default")
      (node (ref "X5") (pin "B5") (pinfunction "-5V_B5") (pintype "passive"))
    )
    (net (code "109") (name "unconnected-(X5A-AEN-PadA11)") (class "Default")
      (node (ref "X5") (pin "A11") (pinfunction "AEN_A11") (pintype "passive"))
    )
    (net (code "110") (name "unconnected-(X5A-BALE-PadB28)") (class "Default")
      (node (ref "X5") (pin "B28") (pinfunction "BALE_B28") (pintype "passive"))
    )
    (net (code "111") (name "unconnected-(X5A-DACK1-PadB17)") (class "Default")
      (node (ref "X5") (pin "B17") (pinfunction "DACK1_B17") (pintype "passive"))
    )
    (net (code "112") (name "unconnected-(X5A-DACK2-PadB26)") (class "Default")
      (node (ref "X5") (pin "B26") (pinfunction "DACK2_B26") (pintype "passive"))
    )
    (net (code "113") (name "unconnected-(X5A-DACK3-PadB15)") (class "Default")
      (node (ref "X5") (pin "B15") (pinfunction "DACK3_B15") (pintype "passive"))
    )
    (net (code "114") (name "unconnected-(X5A-DRQ1-PadB18)") (class "Default")
      (node (ref "X5") (pin "B18") (pinfunction "DRQ1_B18") (pintype "passive"))
    )
    (net (code "115") (name "unconnected-(X5A-DRQ2-PadB6)") (class "Default")
      (node (ref "X5") (pin "B6") (pinfunction "DRQ2_B6") (pintype "passive"))
    )
    (net (code "116") (name "unconnected-(X5A-DRQ3-PadB16)") (class "Default")
      (node (ref "X5") (pin "B16") (pinfunction "DRQ3_B16") (pintype "passive"))
    )
    (net (code "117") (name "unconnected-(X5A-ENDXFR-PadB8)") (class "Default")
      (node (ref "X5") (pin "B8") (pinfunction "ENDXFR_B8") (pintype "passive"))
    )
    (net (code "118") (name "unconnected-(X5A-IOCHCHK-PadA1)") (class "Default")
      (node (ref "X5") (pin "A1") (pinfunction "IOCHCHK_A1") (pintype "passive"))
    )
    (net (code "119") (name "unconnected-(X5A-IOCHRDY-PadA10)") (class "Default")
      (node (ref "X5") (pin "A10") (pinfunction "IOCHRDY_A10") (pintype "passive"))
    )
    (net (code "120") (name "unconnected-(X5A-IOR-PadB14)") (class "Default")
      (node (ref "X5") (pin "B14") (pinfunction "IOR_B14") (pintype "passive"))
    )
    (net (code "121") (name "unconnected-(X5A-IOW-PadB13)") (class "Default")
      (node (ref "X5") (pin "B13") (pinfunction "IOW_B13") (pintype "passive"))
    )
    (net (code "122") (name "unconnected-(X5A-IRQ3-PadB25)") (class "Default")
      (node (ref "X5") (pin "B25") (pinfunction "IRQ3_B25") (pintype "passive"))
    )
    (net (code "123") (name "unconnected-(X5A-IRQ4-PadB24)") (class "Default")
      (node (ref "X5") (pin "B24") (pinfunction "IRQ4_B24") (pintype "passive"))
    )
    (net (code "124") (name "unconnected-(X5A-IRQ5-PadB23)") (class "Default")
      (node (ref "X5") (pin "B23") (pinfunction "IRQ5_B23") (pintype "passive"))
    )
    (net (code "125") (name "unconnected-(X5A-IRQ6-PadB22)") (class "Default")
      (node (ref "X5") (pin "B22") (pinfunction "IRQ6_B22") (pintype "passive"))
    )
    (net (code "126") (name "unconnected-(X5A-IRQ7-PadB21)") (class "Default")
      (node (ref "X5") (pin "B21") (pinfunction "IRQ7_B21") (pintype "passive"))
    )
    (net (code "127") (name "unconnected-(X5A-IRQ9-PadB4)") (class "Default")
      (node (ref "X5") (pin "B4") (pinfunction "IRQ9_B4") (pintype "passive"))
    )
    (net (code "128") (name "unconnected-(X5A-KEY-PadB10)") (class "Default")
      (node (ref "X5") (pin "B10") (pinfunction "KEY_B10") (pintype "passive"))
    )
    (net (code "129") (name "unconnected-(X5A-OSC-PadB30)") (class "Default")
      (node (ref "X5") (pin "B30") (pinfunction "OSC_B30") (pintype "passive"))
    )
    (net (code "130") (name "unconnected-(X5A-REFRESH-PadB19)") (class "Default")
      (node (ref "X5") (pin "B19") (pinfunction "REFRESH_B19") (pintype "passive"))
    )
    (net (code "131") (name "unconnected-(X5A-RESETDRV-PadB2)") (class "Default")
      (node (ref "X5") (pin "B2") (pinfunction "RESETDRV_B2") (pintype "passive"))
    )
    (net (code "132") (name "unconnected-(X5A-SA0-PadA31)") (class "Default")
      (node (ref "X5") (pin "A31") (pinfunction "SA0_A31") (pintype "passive"))
    )
    (net (code "133") (name "unconnected-(X5A-SA1-PadA30)") (class "Default")
      (node (ref "X5") (pin "A30") (pinfunction "SA1_A30") (pintype "passive"))
    )
    (net (code "134") (name "unconnected-(X5A-SA2-PadA29)") (class "Default")
      (node (ref "X5") (pin "A29") (pinfunction "SA2_A29") (pintype "passive"))
    )
    (net (code "135") (name "unconnected-(X5A-SA3-PadA28)") (class "Default")
      (node (ref "X5") (pin "A28") (pinfunction "SA3_A28") (pintype "passive"))
    )
    (net (code "136") (name "unconnected-(X5A-SA4-PadA27)") (class "Default")
      (node (ref "X5") (pin "A27") (pinfunction "SA4_A27") (pintype "passive"))
    )
    (net (code "137") (name "unconnected-(X5A-SA5-PadA26)") (class "Default")
      (node (ref "X5") (pin "A26") (pinfunction "SA5_A26") (pintype "passive"))
    )
    (net (code "138") (name "unconnected-(X5A-SA6-PadA25)") (class "Default")
      (node (ref "X5") (pin "A25") (pinfunction "SA6_A25") (pintype "passive"))
    )
    (net (code "139") (name "unconnected-(X5A-SA7-PadA24)") (class "Default")
      (node (ref "X5") (pin "A24") (pinfunction "SA7_A24") (pintype "passive"))
    )
    (net (code "140") (name "unconnected-(X5A-SA8-PadA23)") (class "Default")
      (node (ref "X5") (pin "A23") (pinfunction "SA8_A23") (pintype "passive"))
    )
    (net (code "141") (name "unconnected-(X5A-SA9-PadA22)") (class "Default")
      (node (ref "X5") (pin "A22") (pinfunction "SA9_A22") (pintype "passive"))
    )
    (net (code "142") (name "unconnected-(X5A-SA10-PadA21)") (class "Default")
      (node (ref "X5") (pin "A21") (pinfunction "SA10_A21") (pintype "passive"))
    )
    (net (code "143") (name "unconnected-(X5A-SA11-PadA20)") (class "Default")
      (node (ref "X5") (pin "A20") (pinfunction "SA11_A20") (pintype "passive"))
    )
    (net (code "144") (name "unconnected-(X5A-SA12-PadA19)") (class "Default")
      (node (ref "X5") (pin "A19") (pinfunction "SA12_A19") (pintype "passive"))
    )
    (net (code "145") (name "unconnected-(X5A-SA13-PadA18)") (class "Default")
      (node (ref "X5") (pin "A18") (pinfunction "SA13_A18") (pintype "passive"))
    )
    (net (code "146") (name "unconnected-(X5A-SA14-PadA17)") (class "Default")
      (node (ref "X5") (pin "A17") (pinfunction "SA14_A17") (pintype "passive"))
    )
    (net (code "147") (name "unconnected-(X5A-SA15-PadA16)") (class "Default")
      (node (ref "X5") (pin "A16") (pinfunction "SA15_A16") (pintype "passive"))
    )
    (net (code "148") (name "unconnected-(X5A-SA16-PadA15)") (class "Default")
      (node (ref "X5") (pin "A15") (pinfunction "SA16_A15") (pintype "passive"))
    )
    (net (code "149") (name "unconnected-(X5A-SA17-PadA14)") (class "Default")
      (node (ref "X5") (pin "A14") (pinfunction "SA17_A14") (pintype "passive"))
    )
    (net (code "150") (name "unconnected-(X5A-SA18-PadA13)") (class "Default")
      (node (ref "X5") (pin "A13") (pinfunction "SA18_A13") (pintype "passive"))
    )
    (net (code "151") (name "unconnected-(X5A-SA19-PadA12)") (class "Default")
      (node (ref "X5") (pin "A12") (pinfunction "SA19_A12") (pintype "passive"))
    )
    (net (code "152") (name "unconnected-(X5A-SD0-PadA9)") (class "Default")
      (node (ref "X5") (pin "A9") (pinfunction "SD0_A9") (pintype "passive"))
    )
    (net (code "153") (name "unconnected-(X5A-SD1-PadA8)") (class "Default")
      (node (ref "X5") (pin "A8") (pinfunction "SD1_A8") (pintype "passive"))
    )
    (net (code "154") (name "unconnected-(X5A-SD2-PadA7)") (class "Default")
      (node (ref "X5") (pin "A7") (pinfunction "SD2_A7") (pintype "passive"))
    )
    (net (code "155") (name "unconnected-(X5A-SD3-PadA6)") (class "Default")
      (node (ref "X5") (pin "A6") (pinfunction "SD3_A6") (pintype "passive"))
    )
    (net (code "156") (name "unconnected-(X5A-SD4-PadA5)") (class "Default")
      (node (ref "X5") (pin "A5") (pinfunction "SD4_A5") (pintype "passive"))
    )
    (net (code "157") (name "unconnected-(X5A-SD5-PadA4)") (class "Default")
      (node (ref "X5") (pin "A4") (pinfunction "SD5_A4") (pintype "passive"))
    )
    (net (code "158") (name "unconnected-(X5A-SD6-PadA3)") (class "Default")
      (node (ref "X5") (pin "A3") (pinfunction "SD6_A3") (pintype "passive"))
    )
    (net (code "159") (name "unconnected-(X5A-SD7-PadA2)") (class "Default")
      (node (ref "X5") (pin "A2") (pinfunction "SD7_A2") (pintype "passive"))
    )
    (net (code "160") (name "unconnected-(X5A-SMEMR-PadB12)") (class "Default")
      (node (ref "X5") (pin "B12") (pinfunction "SMEMR_B12") (pintype "passive"))
    )
    (net (code "161") (name "unconnected-(X5A-SMEMW-PadB11)") (class "Default")
      (node (ref "X5") (pin "B11") (pinfunction "SMEMW_B11") (pintype "passive"))
    )
    (net (code "162") (name "unconnected-(X5A-SYSCLK-PadB20)") (class "Default")
      (node (ref "X5") (pin "B20") (pinfunction "SYSCLK_B20") (pintype "passive"))
    )
    (net (code "163") (name "unconnected-(X5A-TC-PadB27)") (class "Default")
      (node (ref "X5") (pin "B27") (pinfunction "TC_B27") (pintype "passive"))
    )
    (net (code "164") (name "unconnected-(X5B-DACK0-PadD8)") (class "Default")
      (node (ref "X5") (pin "D8") (pinfunction "DACK0_D8") (pintype "passive"))
    )
    (net (code "165") (name "unconnected-(X5B-DACK5-PadD10)") (class "Default")
      (node (ref "X5") (pin "D10") (pinfunction "DACK5_D10") (pintype "passive"))
    )
    (net (code "166") (name "unconnected-(X5B-DACK6-PadD12)") (class "Default")
      (node (ref "X5") (pin "D12") (pinfunction "DACK6_D12") (pintype "passive"))
    )
    (net (code "167") (name "unconnected-(X5B-DACK7-PadD14)") (class "Default")
      (node (ref "X5") (pin "D14") (pinfunction "DACK7_D14") (pintype "passive"))
    )
    (net (code "168") (name "unconnected-(X5B-DRQ0-PadD9)") (class "Default")
      (node (ref "X5") (pin "D9") (pinfunction "DRQ0_D9") (pintype "passive"))
    )
    (net (code "169") (name "unconnected-(X5B-DRQ5-PadD11)") (class "Default")
      (node (ref "X5") (pin "D11") (pinfunction "DRQ5_D11") (pintype "passive"))
    )
    (net (code "170") (name "unconnected-(X5B-DRQ6-PadD13)") (class "Default")
      (node (ref "X5") (pin "D13") (pinfunction "DRQ6_D13") (pintype "passive"))
    )
    (net (code "171") (name "unconnected-(X5B-DRQ7-PadD15)") (class "Default")
      (node (ref "X5") (pin "D15") (pinfunction "DRQ7_D15") (pintype "passive"))
    )
    (net (code "172") (name "unconnected-(X5B-IOCS16-PadD2)") (class "Default")
      (node (ref "X5") (pin "D2") (pinfunction "IOCS16_D2") (pintype "passive"))
    )
    (net (code "173") (name "unconnected-(X5B-IRQ10-PadD3)") (class "Default")
      (node (ref "X5") (pin "D3") (pinfunction "IRQ10_D3") (pintype "passive"))
    )
    (net (code "174") (name "unconnected-(X5B-IRQ11-PadD4)") (class "Default")
      (node (ref "X5") (pin "D4") (pinfunction "IRQ11_D4") (pintype "passive"))
    )
    (net (code "175") (name "unconnected-(X5B-IRQ12-PadD5)") (class "Default")
      (node (ref "X5") (pin "D5") (pinfunction "IRQ12_D5") (pintype "passive"))
    )
    (net (code "176") (name "unconnected-(X5B-IRQ14-PadD7)") (class "Default")
      (node (ref "X5") (pin "D7") (pinfunction "IRQ14_D7") (pintype "passive"))
    )
    (net (code "177") (name "unconnected-(X5B-IRQ15-PadD6)") (class "Default")
      (node (ref "X5") (pin "D6") (pinfunction "IRQ15_D6") (pintype "passive"))
    )
    (net (code "178") (name "unconnected-(X5B-KEY-PadC19)") (class "Default")
      (node (ref "X5") (pin "C19") (pinfunction "KEY_C19") (pintype "passive"))
    )
    (net (code "179") (name "unconnected-(X5B-LA17-PadC8)") (class "Default")
      (node (ref "X5") (pin "C8") (pinfunction "LA17_C8") (pintype "passive"))
    )
    (net (code "180") (name "unconnected-(X5B-LA18-PadC7)") (class "Default")
      (node (ref "X5") (pin "C7") (pinfunction "LA18_C7") (pintype "passive"))
    )
    (net (code "181") (name "unconnected-(X5B-LA19-PadC6)") (class "Default")
      (node (ref "X5") (pin "C6") (pinfunction "LA19_C6") (pintype "passive"))
    )
    (net (code "182") (name "unconnected-(X5B-LA20-PadC5)") (class "Default")
      (node (ref "X5") (pin "C5") (pinfunction "LA20_C5") (pintype "passive"))
    )
    (net (code "183") (name "unconnected-(X5B-LA21-PadC4)") (class "Default")
      (node (ref "X5") (pin "C4") (pinfunction "LA21_C4") (pintype "passive"))
    )
    (net (code "184") (name "unconnected-(X5B-LA22-PadC3)") (class "Default")
      (node (ref "X5") (pin "C3") (pinfunction "LA22_C3") (pintype "passive"))
    )
    (net (code "185") (name "unconnected-(X5B-LA23-PadC2)") (class "Default")
      (node (ref "X5") (pin "C2") (pinfunction "LA23_C2") (pintype "passive"))
    )
    (net (code "186") (name "unconnected-(X5B-MASTER-PadD17)") (class "Default")
      (node (ref "X5") (pin "D17") (pinfunction "MASTER_D17") (pintype "passive"))
    )
    (net (code "187") (name "unconnected-(X5B-MEMCS16-PadD1)") (class "Default")
      (node (ref "X5") (pin "D1") (pinfunction "MEMCS16_D1") (pintype "passive"))
    )
    (net (code "188") (name "unconnected-(X5B-MEMR-PadC9)") (class "Default")
      (node (ref "X5") (pin "C9") (pinfunction "MEMR_C9") (pintype "passive"))
    )
    (net (code "189") (name "unconnected-(X5B-MEMW-PadC10)") (class "Default")
      (node (ref "X5") (pin "C10") (pinfunction "MEMW_C10") (pintype "passive"))
    )
    (net (code "190") (name "unconnected-(X5B-SBHE-PadC1)") (class "Default")
      (node (ref "X5") (pin "C1") (pinfunction "SBHE_C1") (pintype "passive"))
    )
    (net (code "191") (name "unconnected-(X5B-SD8-PadC11)") (class "Default")
      (node (ref "X5") (pin "C11") (pinfunction "SD8_C11") (pintype "passive"))
    )
    (net (code "192") (name "unconnected-(X5B-SD9-PadC12)") (class "Default")
      (node (ref "X5") (pin "C12") (pinfunction "SD9_C12") (pintype "passive"))
    )
    (net (code "193") (name "unconnected-(X5B-SD10-PadC13)") (class "Default")
      (node (ref "X5") (pin "C13") (pinfunction "SD10_C13") (pintype "passive"))
    )
    (net (code "194") (name "unconnected-(X5B-SD11-PadC14)") (class "Default")
      (node (ref "X5") (pin "C14") (pinfunction "SD11_C14") (pintype "passive"))
    )
    (net (code "195") (name "unconnected-(X5B-SD12-PadC15)") (class "Default")
      (node (ref "X5") (pin "C15") (pinfunction "SD12_C15") (pintype "passive"))
    )
    (net (code "196") (name "unconnected-(X5B-SD13-PadC16)") (class "Default")
      (node (ref "X5") (pin "C16") (pinfunction "SD13_C16") (pintype "passive"))
    )
    (net (code "197") (name "unconnected-(X5B-SD14-PadC17)") (class "Default")
      (node (ref "X5") (pin "C17") (pinfunction "SD14_C17") (pintype "passive"))
    )
    (net (code "198") (name "unconnected-(X5B-SD15-PadC18)") (class "Default")
      (node (ref "X5") (pin "C18") (pinfunction "SD15_C18") (pintype "passive"))
    )
  )
)
